# MOSFET_Board.net
KiCad netlist of a schematic drawn in EAGLE
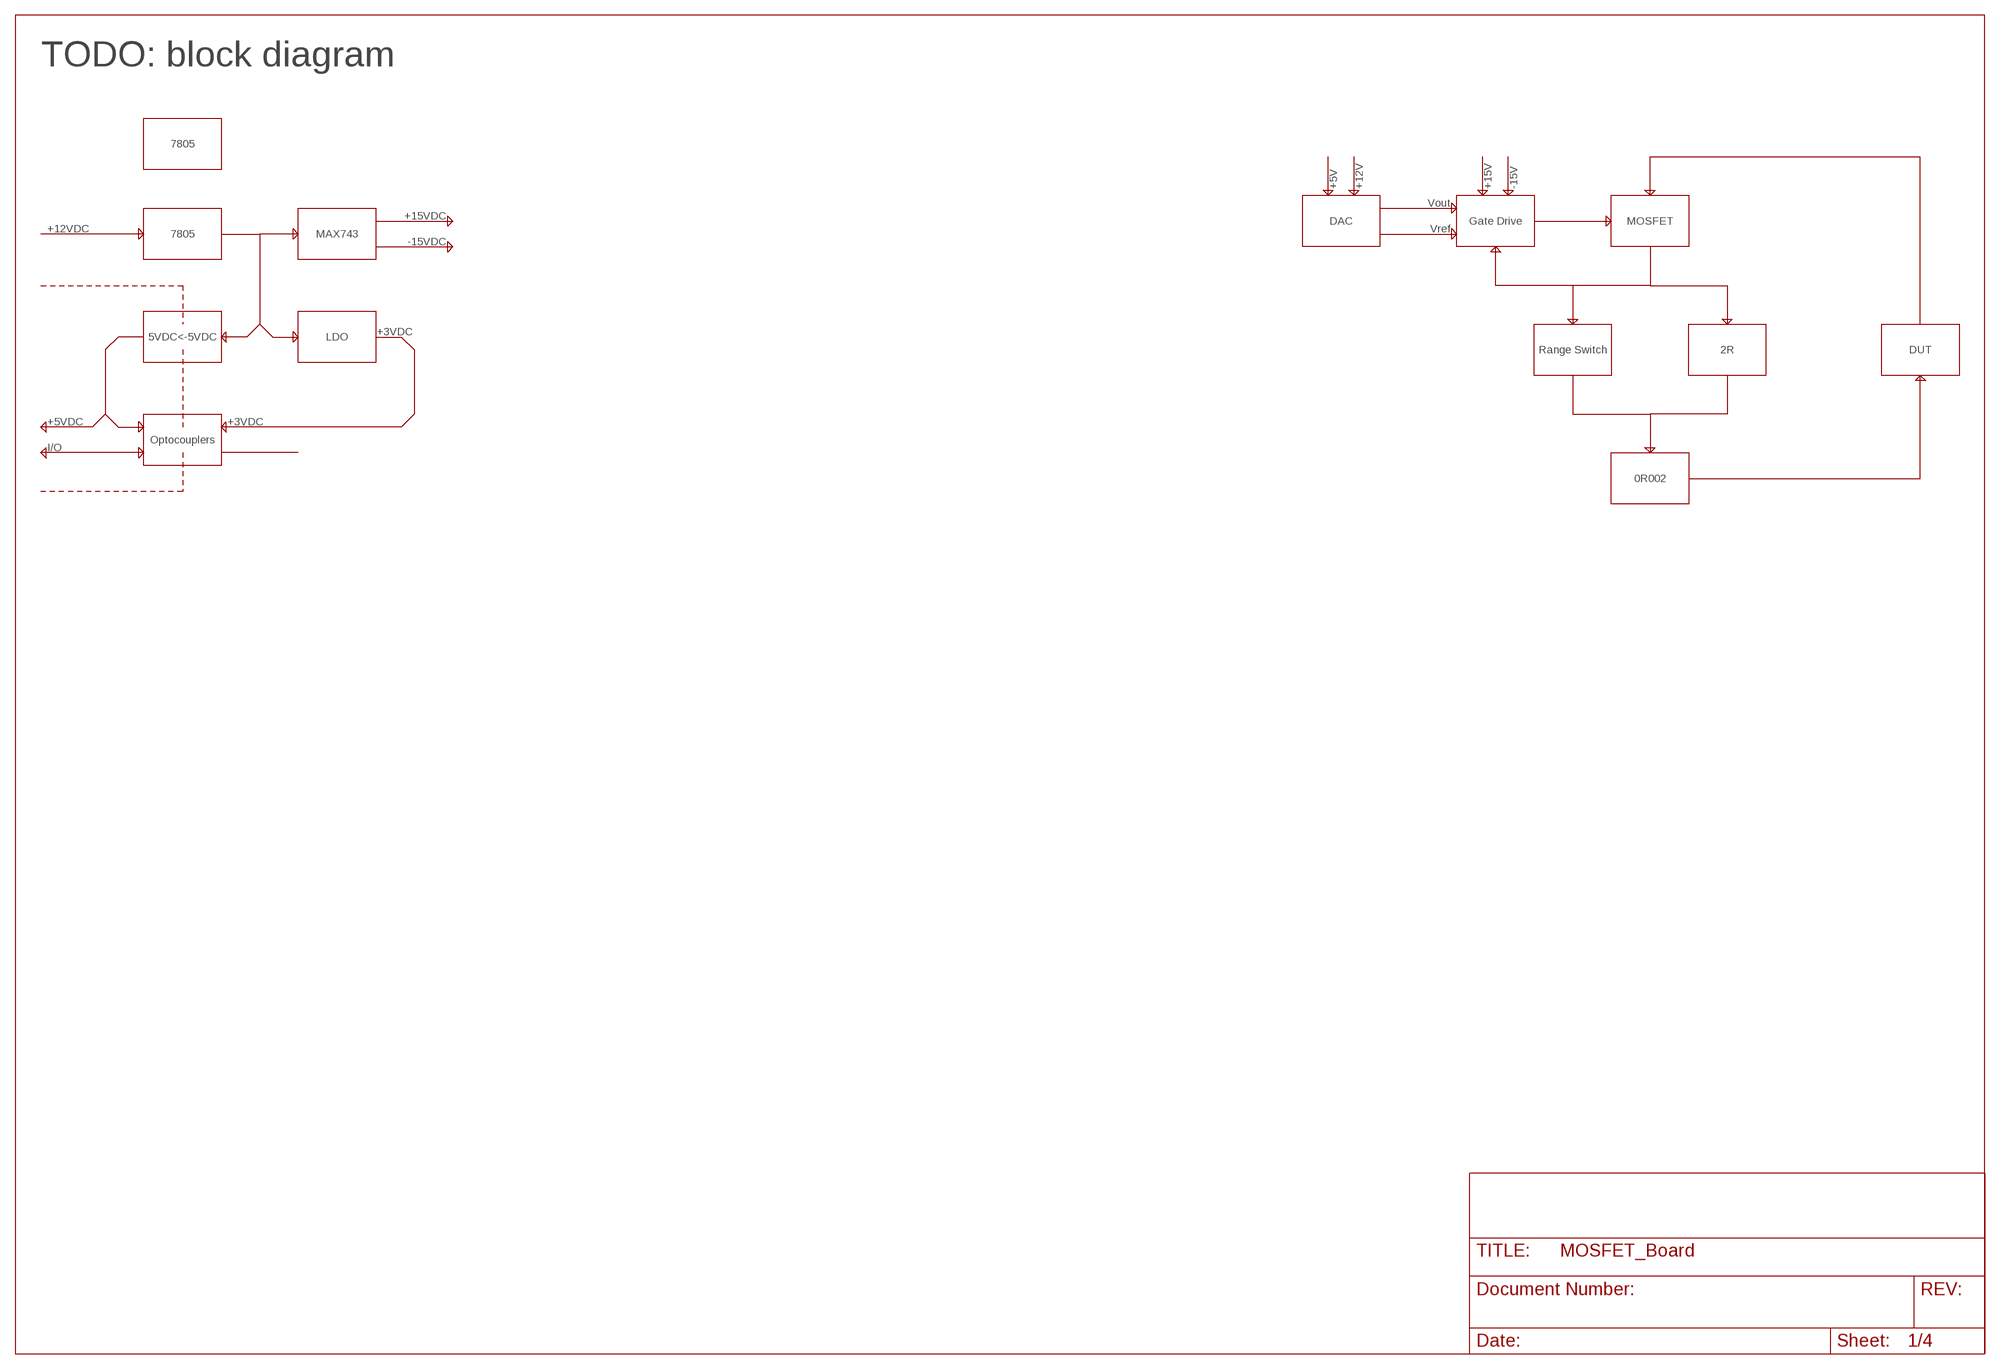
[diagram p0: schematic, sheet 1]
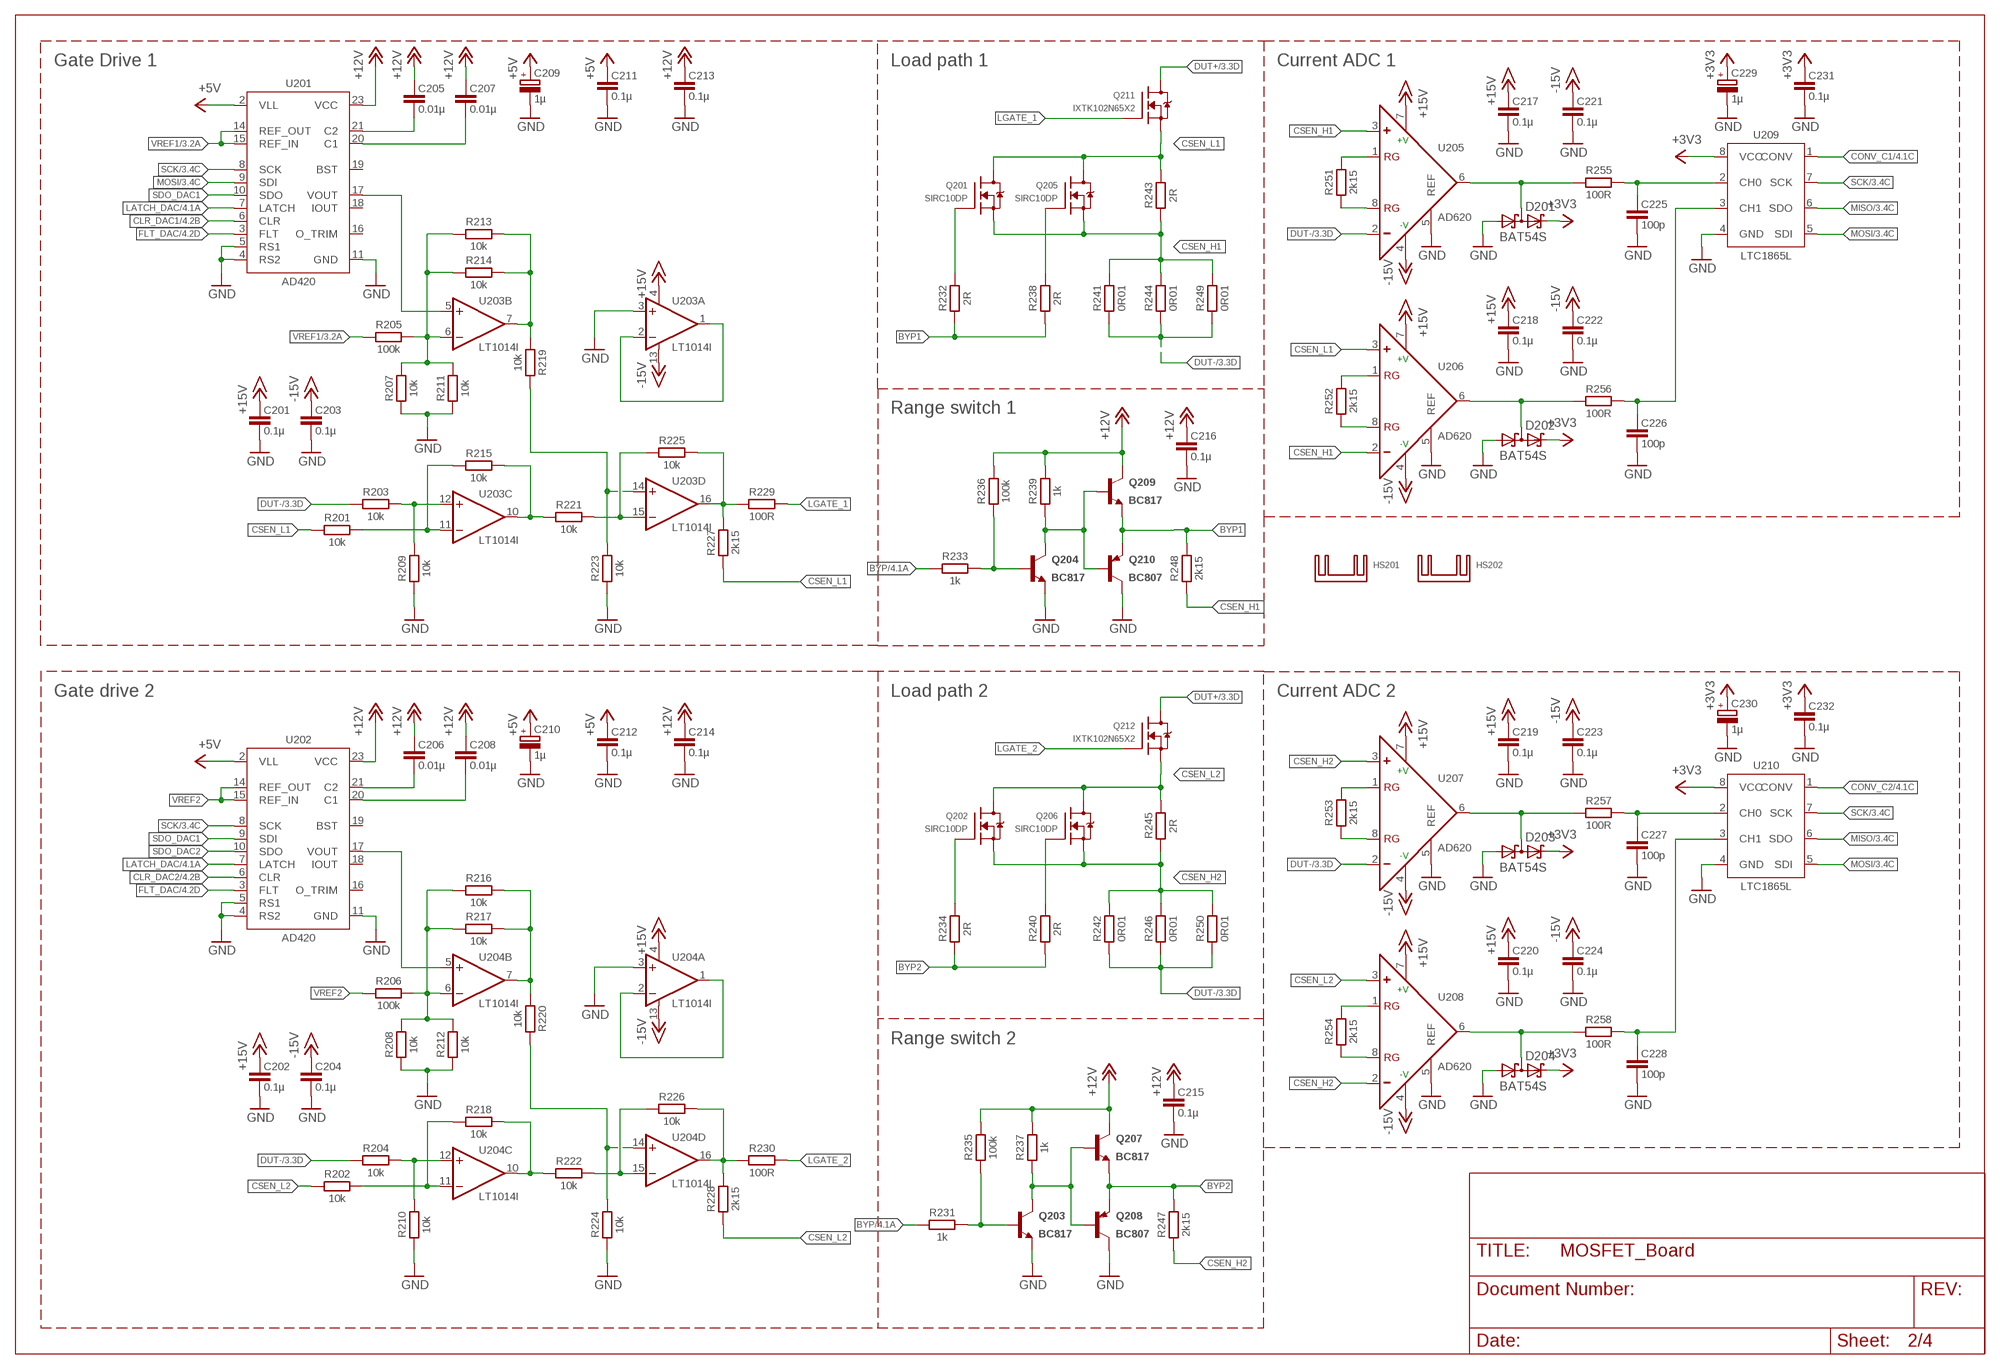
[diagram p1: schematic, sheet 2]
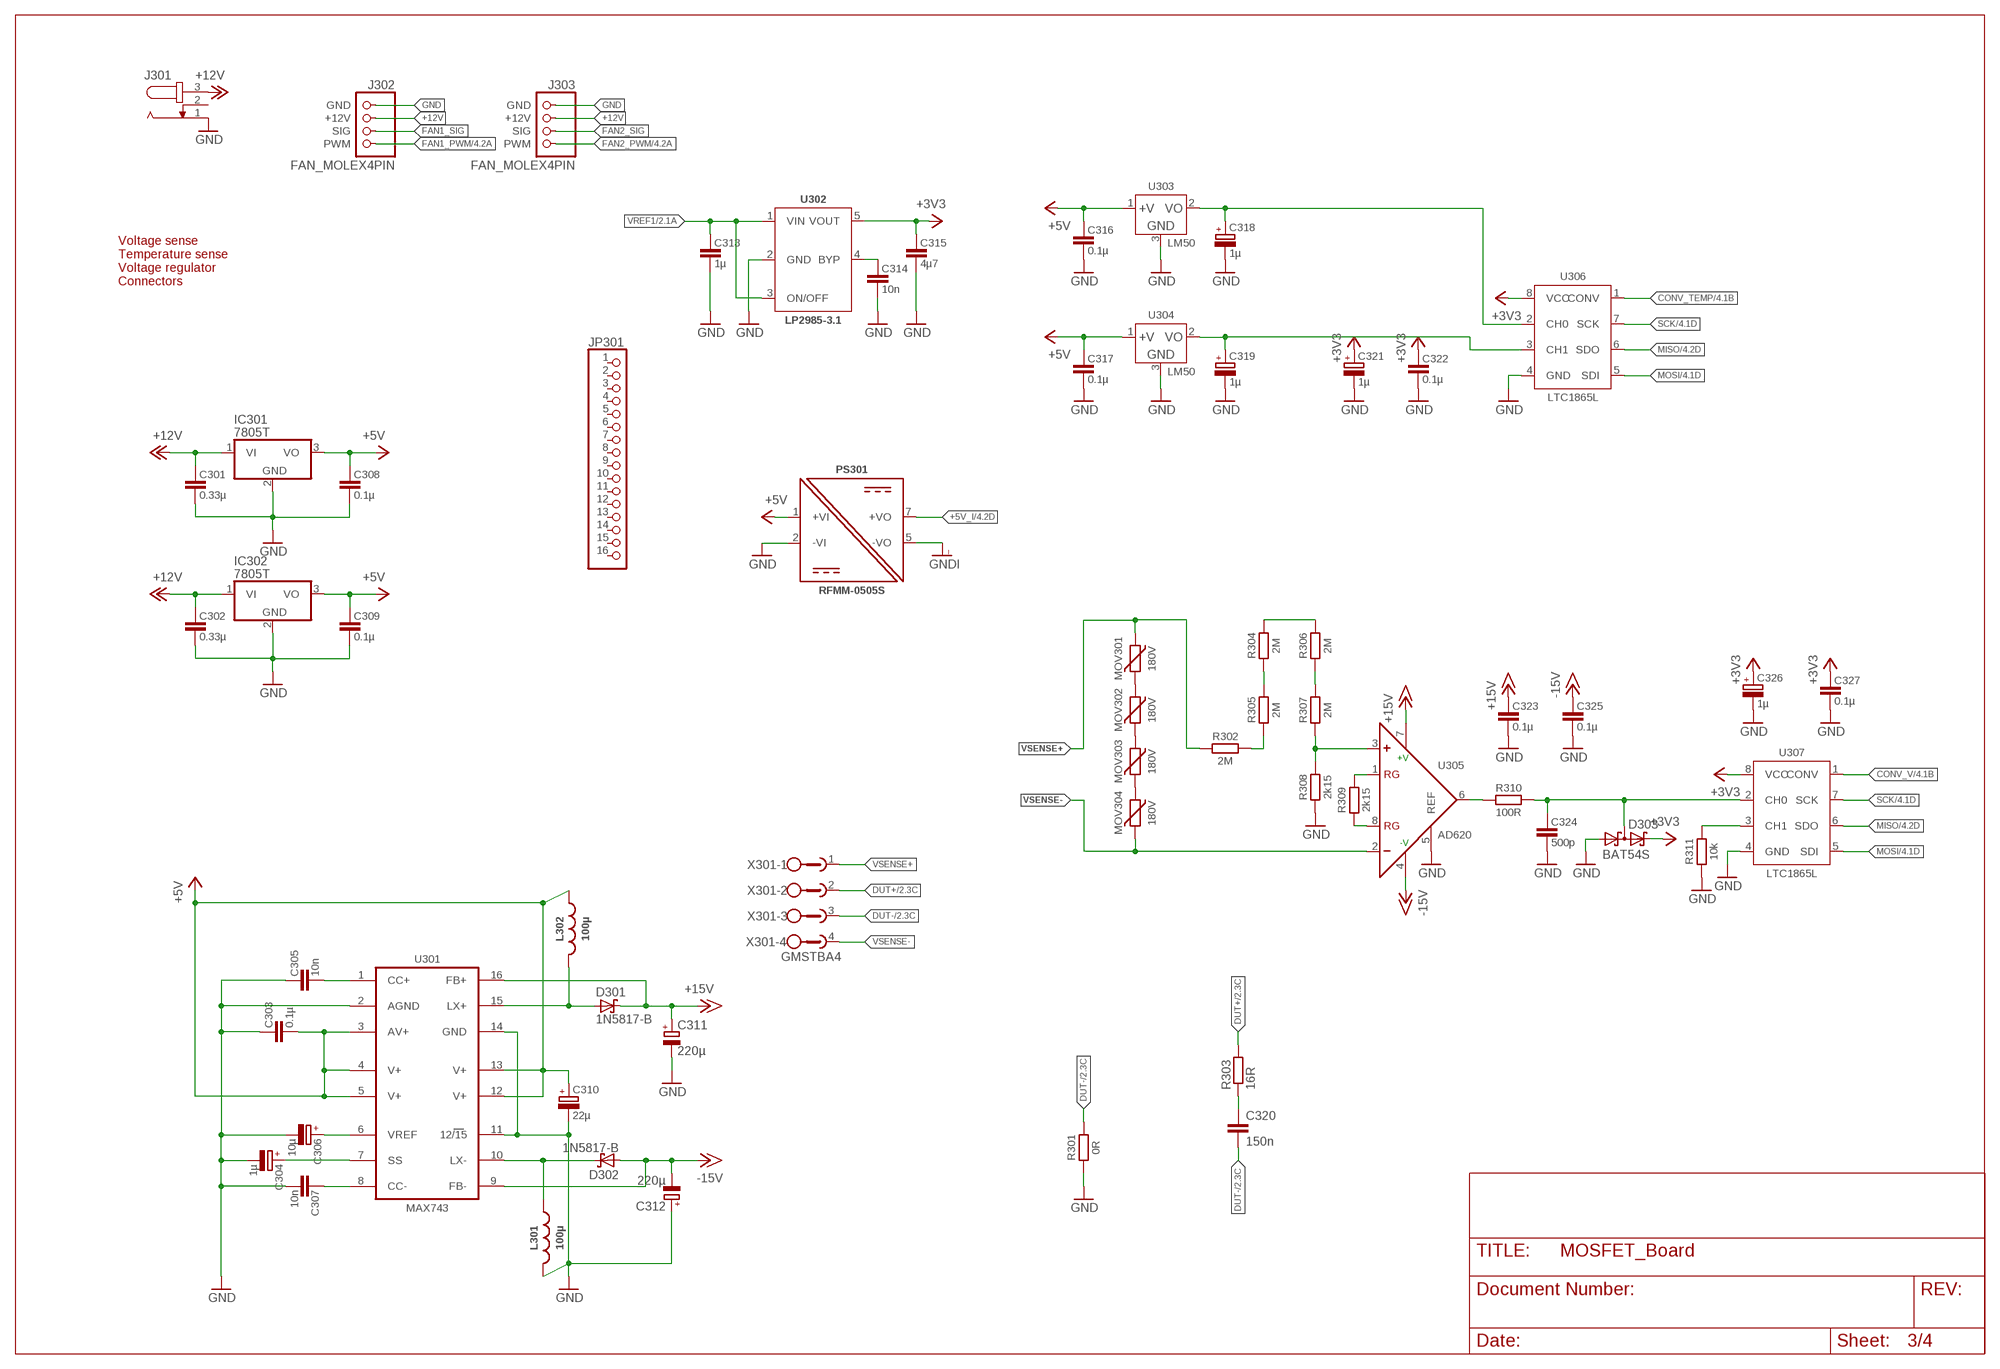
[diagram p2: schematic, sheet 3]
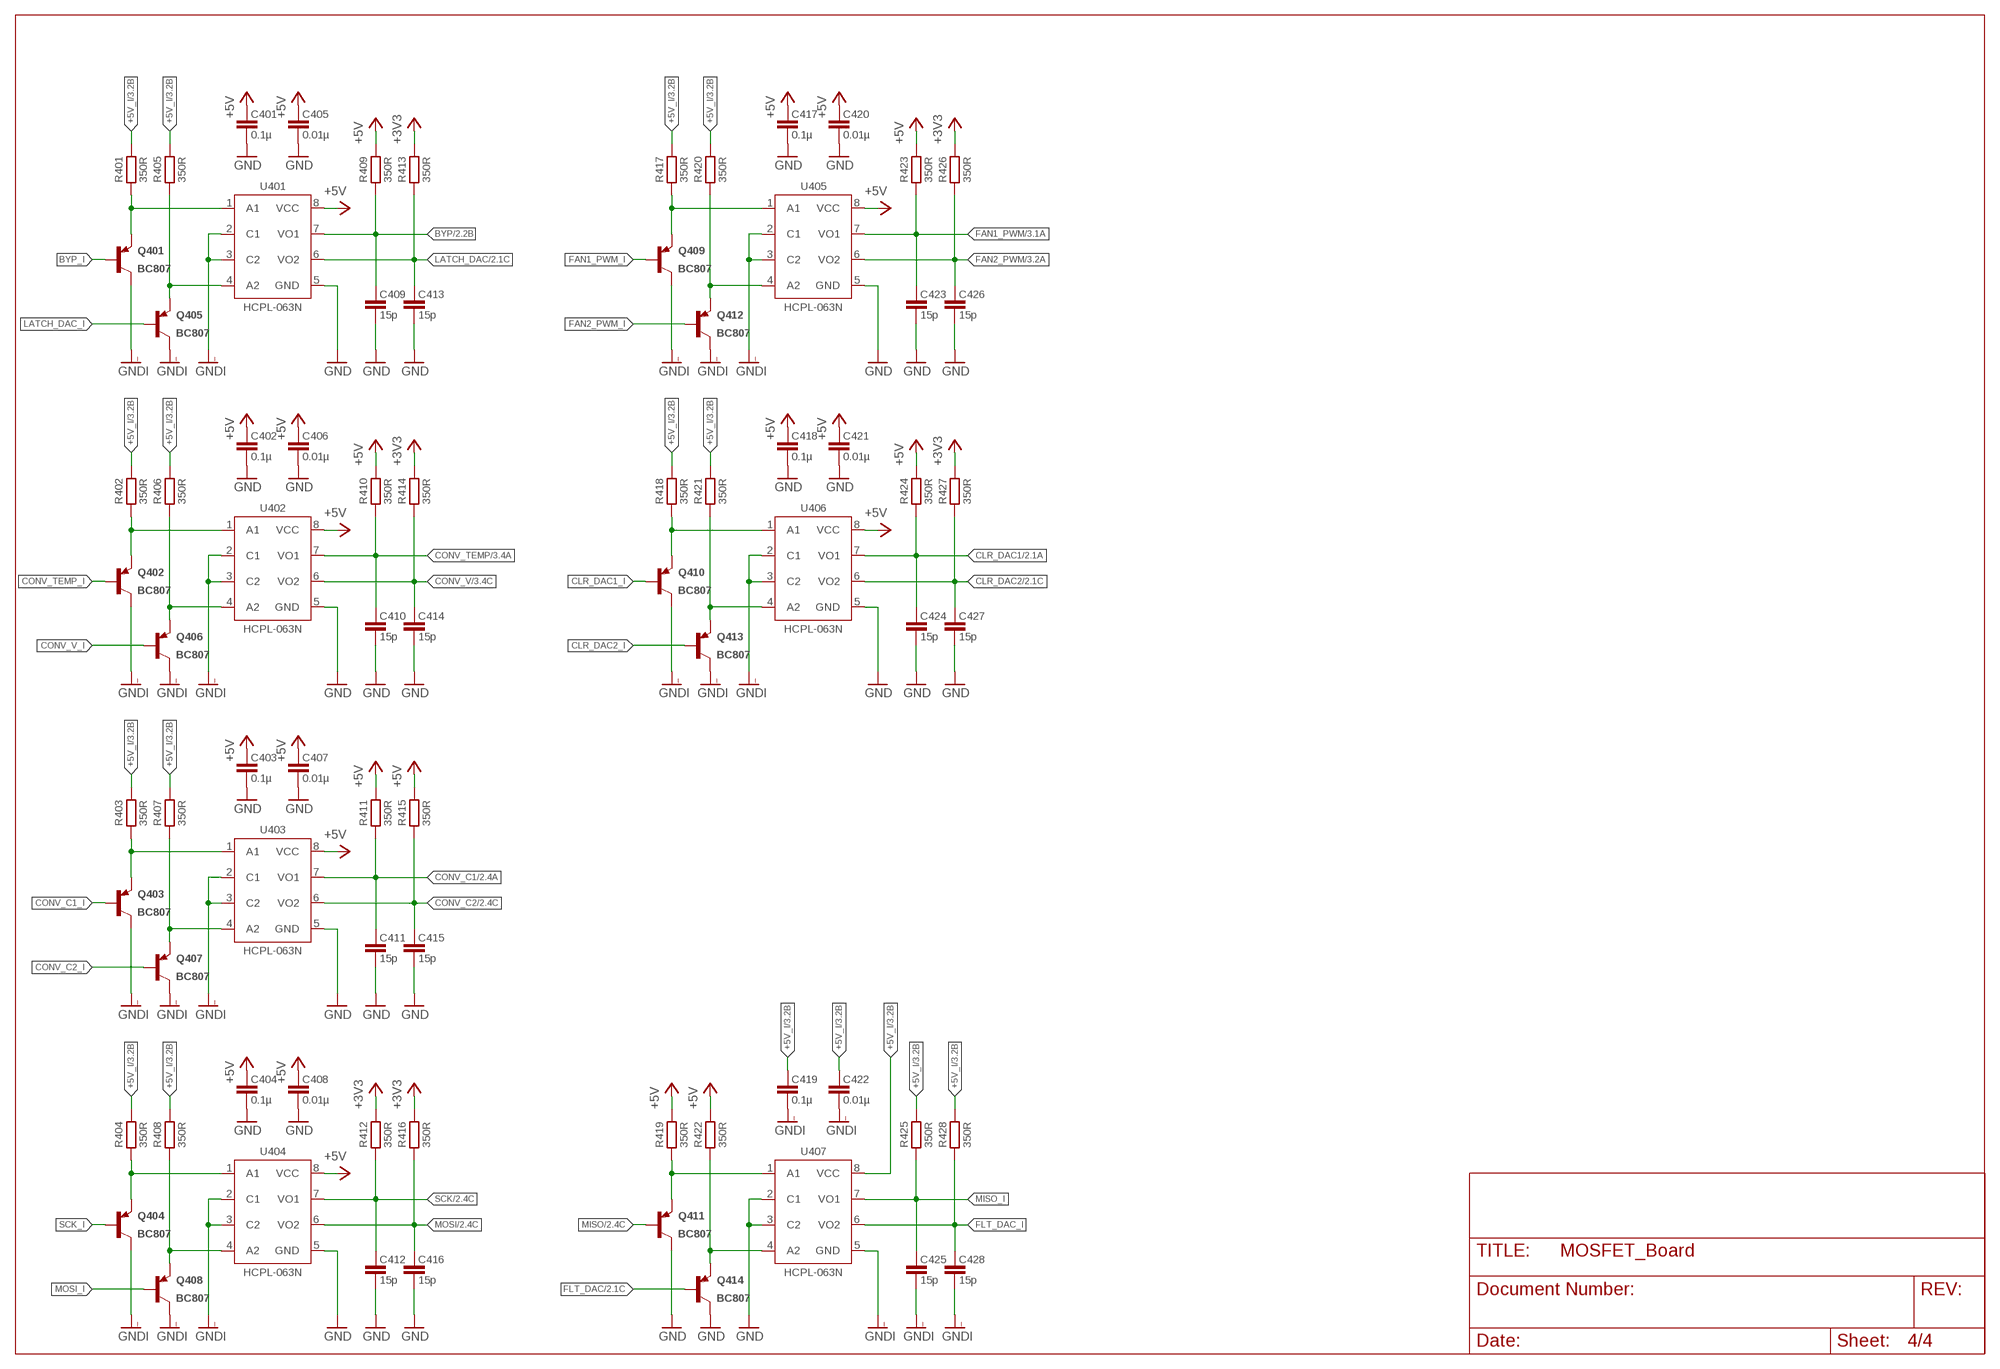
[diagram p3: schematic, sheet 4]

(export (version "E")
  (design (tool "Eeschema 10.0.6"))
  (components
    (comp (ref "C401")
      (value "0.1µ")
      (footprint "eagle-import:C1608")
      (libsource (lib "eagle-import") (part "C-EU-1608"))
    )
    (comp (ref "C402")
      (value "0.1µ")
      (footprint "eagle-import:C1608")
      (libsource (lib "eagle-import") (part "C-EU-1608"))
    )
    (comp (ref "C403")
      (value "0.1µ")
      (footprint "eagle-import:C1608")
      (libsource (lib "eagle-import") (part "C-EU-1608"))
    )
    (comp (ref "C404")
      (value "0.1µ")
      (footprint "eagle-import:C1608")
      (libsource (lib "eagle-import") (part "C-EU-1608"))
    )
    (comp (ref "C405")
      (value "0.01µ")
      (footprint "eagle-import:C3216")
      (libsource (lib "eagle-import") (part "C-EU-3216"))
    )
    (comp (ref "C406")
      (value "0.01µ")
      (footprint "eagle-import:C3216")
      (libsource (lib "eagle-import") (part "C-EU-3216"))
    )
    (comp (ref "C407")
      (value "0.01µ")
      (footprint "eagle-import:C3216")
      (libsource (lib "eagle-import") (part "C-EU-3216"))
    )
    (comp (ref "C408")
      (value "0.01µ")
      (footprint "eagle-import:C3216")
      (libsource (lib "eagle-import") (part "C-EU-3216"))
    )
    (comp (ref "C409")
      (value "15p")
      (footprint "eagle-import:C1608")
      (libsource (lib "eagle-import") (part "C-EU-1608"))
    )
    (comp (ref "C410")
      (value "15p")
      (footprint "eagle-import:C1608")
      (libsource (lib "eagle-import") (part "C-EU-1608"))
    )
    (comp (ref "C411")
      (value "15p")
      (footprint "eagle-import:C1608")
      (libsource (lib "eagle-import") (part "C-EU-1608"))
    )
    (comp (ref "C412")
      (value "15p")
      (footprint "eagle-import:C1608")
      (libsource (lib "eagle-import") (part "C-EU-1608"))
    )
    (comp (ref "C413")
      (value "15p")
      (footprint "eagle-import:C1608")
      (libsource (lib "eagle-import") (part "C-EU-1608"))
    )
    (comp (ref "C414")
      (value "15p")
      (footprint "eagle-import:C1608")
      (libsource (lib "eagle-import") (part "C-EU-1608"))
    )
    (comp (ref "C415")
      (value "15p")
      (footprint "eagle-import:C1608")
      (libsource (lib "eagle-import") (part "C-EU-1608"))
    )
    (comp (ref "C416")
      (value "15p")
      (footprint "eagle-import:C1608")
      (libsource (lib "eagle-import") (part "C-EU-1608"))
    )
    (comp (ref "C417")
      (value "0.1µ")
      (footprint "eagle-import:C1608")
      (libsource (lib "eagle-import") (part "C-EU-1608"))
    )
    (comp (ref "C418")
      (value "0.1µ")
      (footprint "eagle-import:C1608")
      (libsource (lib "eagle-import") (part "C-EU-1608"))
    )
    (comp (ref "C419")
      (value "0.1µ")
      (footprint "eagle-import:C1608")
      (libsource (lib "eagle-import") (part "C-EU-1608"))
    )
    (comp (ref "C420")
      (value "0.01µ")
      (footprint "eagle-import:C3216")
      (libsource (lib "eagle-import") (part "C-EU-3216"))
    )
    (comp (ref "C421")
      (value "0.01µ")
      (footprint "eagle-import:C3216")
      (libsource (lib "eagle-import") (part "C-EU-3216"))
    )
    (comp (ref "C422")
      (value "0.01µ")
      (footprint "eagle-import:C3216")
      (libsource (lib "eagle-import") (part "C-EU-3216"))
    )
    (comp (ref "C423")
      (value "15p")
      (footprint "eagle-import:C1608")
      (libsource (lib "eagle-import") (part "C-EU-1608"))
    )
    (comp (ref "C424")
      (value "15p")
      (footprint "eagle-import:C1608")
      (libsource (lib "eagle-import") (part "C-EU-1608"))
    )
    (comp (ref "C425")
      (value "15p")
      (footprint "eagle-import:C1608")
      (libsource (lib "eagle-import") (part "C-EU-1608"))
    )
    (comp (ref "C426")
      (value "15p")
      (footprint "eagle-import:C1608")
      (libsource (lib "eagle-import") (part "C-EU-1608"))
    )
    (comp (ref "C427")
      (value "15p")
      (footprint "eagle-import:C1608")
      (libsource (lib "eagle-import") (part "C-EU-1608"))
    )
    (comp (ref "C428")
      (value "15p")
      (footprint "eagle-import:C1608")
      (libsource (lib "eagle-import") (part "C-EU-1608"))
    )
    (comp (ref "Q401")
      (value "BC807")
      (footprint "eagle-import:SOT23")
      (libsource (lib "eagle-import") (part "BC807"))
    )
    (comp (ref "Q402")
      (value "BC807")
      (footprint "eagle-import:SOT23")
      (libsource (lib "eagle-import") (part "BC807"))
    )
    (comp (ref "Q403")
      (value "BC807")
      (footprint "eagle-import:SOT23")
      (libsource (lib "eagle-import") (part "BC807"))
    )
    (comp (ref "Q404")
      (value "BC807")
      (footprint "eagle-import:SOT23")
      (libsource (lib "eagle-import") (part "BC807"))
    )
    (comp (ref "Q405")
      (value "BC807")
      (footprint "eagle-import:SOT23")
      (libsource (lib "eagle-import") (part "BC807"))
    )
    (comp (ref "Q406")
      (value "BC807")
      (footprint "eagle-import:SOT23")
      (libsource (lib "eagle-import") (part "BC807"))
    )
    (comp (ref "Q407")
      (value "BC807")
      (footprint "eagle-import:SOT23")
      (libsource (lib "eagle-import") (part "BC807"))
    )
    (comp (ref "Q408")
      (value "BC807")
      (footprint "eagle-import:SOT23")
      (libsource (lib "eagle-import") (part "BC807"))
    )
    (comp (ref "Q409")
      (value "BC807")
      (footprint "eagle-import:SOT23")
      (libsource (lib "eagle-import") (part "BC807"))
    )
    (comp (ref "Q410")
      (value "BC807")
      (footprint "eagle-import:SOT23")
      (libsource (lib "eagle-import") (part "BC807"))
    )
    (comp (ref "Q411")
      (value "BC807")
      (footprint "eagle-import:SOT23")
      (libsource (lib "eagle-import") (part "BC807"))
    )
    (comp (ref "Q412")
      (value "BC807")
      (footprint "eagle-import:SOT23")
      (libsource (lib "eagle-import") (part "BC807"))
    )
    (comp (ref "Q413")
      (value "BC807")
      (footprint "eagle-import:SOT23")
      (libsource (lib "eagle-import") (part "BC807"))
    )
    (comp (ref "Q414")
      (value "BC807")
      (footprint "eagle-import:SOT23")
      (libsource (lib "eagle-import") (part "BC807"))
    )
    (comp (ref "R401")
      (value "350R")
      (footprint "eagle-import:R1608")
      (libsource (lib "eagle-import") (part "R-EU-1608"))
    )
    (comp (ref "R402")
      (value "350R")
      (footprint "eagle-import:R1608")
      (libsource (lib "eagle-import") (part "R-EU-1608"))
    )
    (comp (ref "R403")
      (value "350R")
      (footprint "eagle-import:R1608")
      (libsource (lib "eagle-import") (part "R-EU-1608"))
    )
    (comp (ref "R404")
      (value "350R")
      (footprint "eagle-import:R1608")
      (libsource (lib "eagle-import") (part "R-EU-1608"))
    )
    (comp (ref "R405")
      (value "350R")
      (footprint "eagle-import:R1608")
      (libsource (lib "eagle-import") (part "R-EU-1608"))
    )
    (comp (ref "R406")
      (value "350R")
      (footprint "eagle-import:R1608")
      (libsource (lib "eagle-import") (part "R-EU-1608"))
    )
    (comp (ref "R407")
      (value "350R")
      (footprint "eagle-import:R1608")
      (libsource (lib "eagle-import") (part "R-EU-1608"))
    )
    (comp (ref "R408")
      (value "350R")
      (footprint "eagle-import:R1608")
      (libsource (lib "eagle-import") (part "R-EU-1608"))
    )
    (comp (ref "R409")
      (value "350R")
      (footprint "eagle-import:R1608")
      (libsource (lib "eagle-import") (part "R-EU-1608"))
    )
    (comp (ref "R410")
      (value "350R")
      (footprint "eagle-import:R1608")
      (libsource (lib "eagle-import") (part "R-EU-1608"))
    )
    (comp (ref "R411")
      (value "350R")
      (footprint "eagle-import:R1608")
      (libsource (lib "eagle-import") (part "R-EU-1608"))
    )
    (comp (ref "R412")
      (value "350R")
      (footprint "eagle-import:R1608")
      (libsource (lib "eagle-import") (part "R-EU-1608"))
    )
    (comp (ref "R413")
      (value "350R")
      (footprint "eagle-import:R1608")
      (libsource (lib "eagle-import") (part "R-EU-1608"))
    )
    (comp (ref "R414")
      (value "350R")
      (footprint "eagle-import:R1608")
      (libsource (lib "eagle-import") (part "R-EU-1608"))
    )
    (comp (ref "R415")
      (value "350R")
      (footprint "eagle-import:R1608")
      (libsource (lib "eagle-import") (part "R-EU-1608"))
    )
    (comp (ref "R416")
      (value "350R")
      (footprint "eagle-import:R1608")
      (libsource (lib "eagle-import") (part "R-EU-1608"))
    )
    (comp (ref "R417")
      (value "350R")
      (footprint "eagle-import:R1608")
      (libsource (lib "eagle-import") (part "R-EU-1608"))
    )
    (comp (ref "R418")
      (value "350R")
      (footprint "eagle-import:R1608")
      (libsource (lib "eagle-import") (part "R-EU-1608"))
    )
    (comp (ref "R419")
      (value "350R")
      (footprint "eagle-import:R1608")
      (libsource (lib "eagle-import") (part "R-EU-1608"))
    )
    (comp (ref "R420")
      (value "350R")
      (footprint "eagle-import:R1608")
      (libsource (lib "eagle-import") (part "R-EU-1608"))
    )
    (comp (ref "R421")
      (value "350R")
      (footprint "eagle-import:R1608")
      (libsource (lib "eagle-import") (part "R-EU-1608"))
    )
    (comp (ref "R422")
      (value "350R")
      (footprint "eagle-import:R1608")
      (libsource (lib "eagle-import") (part "R-EU-1608"))
    )
    (comp (ref "R423")
      (value "350R")
      (footprint "eagle-import:R1608")
      (libsource (lib "eagle-import") (part "R-EU-1608"))
    )
    (comp (ref "R424")
      (value "350R")
      (footprint "eagle-import:R1608")
      (libsource (lib "eagle-import") (part "R-EU-1608"))
    )
    (comp (ref "R425")
      (value "350R")
      (footprint "eagle-import:R1608")
      (libsource (lib "eagle-import") (part "R-EU-1608"))
    )
    (comp (ref "R426")
      (value "350R")
      (footprint "eagle-import:R1608")
      (libsource (lib "eagle-import") (part "R-EU-1608"))
    )
    (comp (ref "R427")
      (value "350R")
      (footprint "eagle-import:R1608")
      (libsource (lib "eagle-import") (part "R-EU-1608"))
    )
    (comp (ref "R428")
      (value "350R")
      (footprint "eagle-import:R1608")
      (libsource (lib "eagle-import") (part "R-EU-1608"))
    )
    (comp (ref "U401")
      (value "HCPL-063N")
      (footprint "eagle-import:SO8")
      (libsource (lib "eagle-import") (part "HCPL-063N"))
    )
    (comp (ref "U402")
      (value "HCPL-063N")
      (footprint "eagle-import:SO8")
      (libsource (lib "eagle-import") (part "HCPL-063N"))
    )
    (comp (ref "U403")
      (value "HCPL-063N")
      (footprint "eagle-import:SO8")
      (libsource (lib "eagle-import") (part "HCPL-063N"))
    )
    (comp (ref "U404")
      (value "HCPL-063N")
      (footprint "eagle-import:SO8")
      (libsource (lib "eagle-import") (part "HCPL-063N"))
    )
    (comp (ref "U405")
      (value "HCPL-063N")
      (footprint "eagle-import:SO8")
      (libsource (lib "eagle-import") (part "HCPL-063N"))
    )
    (comp (ref "U406")
      (value "HCPL-063N")
      (footprint "eagle-import:SO8")
      (libsource (lib "eagle-import") (part "HCPL-063N"))
    )
    (comp (ref "U407")
      (value "HCPL-063N")
      (footprint "eagle-import:SO8")
      (libsource (lib "eagle-import") (part "HCPL-063N"))
    )
    (comp (ref "C301")
      (value "0.33µ")
      (footprint "eagle-import:C3216")
      (libsource (lib "eagle-import") (part "C-EU-3216"))
    )
    (comp (ref "C302")
      (value "0.33µ")
      (footprint "eagle-import:C3216")
      (libsource (lib "eagle-import") (part "C-EU-3216"))
    )
    (comp (ref "C303")
      (value "0.1µ")
      (footprint "eagle-import:C3216")
      (libsource (lib "eagle-import") (part "C-EU-3216"))
    )
    (comp (ref "C304")
      (value "1µ")
      (footprint "eagle-import:CT3216")
      (libsource (lib "eagle-import") (part "CPOL-3216-A"))
    )
    (comp (ref "C305")
      (value "10n")
      (footprint "eagle-import:C2012")
      (libsource (lib "eagle-import") (part "C-EU-2012"))
    )
    (comp (ref "C306")
      (value "10µ")
      (footprint "eagle-import:CT6032")
      (libsource (lib "eagle-import") (part "CPOL-6032-C"))
    )
    (comp (ref "C307")
      (value "10n")
      (footprint "eagle-import:C2012")
      (libsource (lib "eagle-import") (part "C-EU-2012"))
    )
    (comp (ref "C308")
      (value "0.1µ")
      (footprint "eagle-import:C1608")
      (libsource (lib "eagle-import") (part "C-EU-1608"))
    )
    (comp (ref "C309")
      (value "0.1µ")
      (footprint "eagle-import:C1608")
      (libsource (lib "eagle-import") (part "C-EU-1608"))
    )
    (comp (ref "C310")
      (value "22µ")
      (footprint "eagle-import:CT6032")
      (libsource (lib "eagle-import") (part "CPOL-6032-C"))
    )
    (comp (ref "C311")
      (value "220µ")
      (footprint "eagle-import:E3,5-10")
      (libsource (lib "eagle-import") (part "CPOL-EUE3.5-10"))
    )
    (comp (ref "C312")
      (value "220µ")
      (footprint "eagle-import:E3,5-10")
      (libsource (lib "eagle-import") (part "CPOL-EUE3.5-10"))
    )
    (comp (ref "C313")
      (value "1µ")
      (footprint "eagle-import:C3216")
      (libsource (lib "eagle-import") (part "C-EU-3216"))
    )
    (comp (ref "C314")
      (value "10n")
      (footprint "eagle-import:C2012")
      (libsource (lib "eagle-import") (part "C-EU-2012"))
    )
    (comp (ref "C315")
      (value "4µ7")
      (footprint "eagle-import:C3216")
      (libsource (lib "eagle-import") (part "C-EU-3216"))
    )
    (comp (ref "C316")
      (value "0.1µ")
      (footprint "eagle-import:C3216")
      (libsource (lib "eagle-import") (part "C-EU-3216"))
    )
    (comp (ref "C317")
      (value "0.1µ")
      (footprint "eagle-import:C3216")
      (libsource (lib "eagle-import") (part "C-EU-3216"))
    )
    (comp (ref "C318")
      (value "1µ")
      (footprint "eagle-import:CT3216")
      (libsource (lib "eagle-import") (part "CPOL-3216-A"))
    )
    (comp (ref "C319")
      (value "1µ")
      (footprint "eagle-import:CT3216")
      (libsource (lib "eagle-import") (part "CPOL-3216-A"))
    )
    (comp (ref "C320")
      (value "150n")
      (footprint "eagle-import:C050-030X075")
      (libsource (lib "eagle-import") (part "C-EU050-030X075"))
    )
    (comp (ref "C321")
      (value "1µ")
      (footprint "eagle-import:CT3216")
      (libsource (lib "eagle-import") (part "CPOL-3216-A"))
    )
    (comp (ref "C322")
      (value "0.1µ")
      (footprint "eagle-import:C3216")
      (libsource (lib "eagle-import") (part "C-EU-3216"))
    )
    (comp (ref "C323")
      (value "0.1µ")
      (footprint "eagle-import:C3216")
      (libsource (lib "eagle-import") (part "C-EU-3216"))
    )
    (comp (ref "C324")
      (value "500p")
      (footprint "eagle-import:C1608")
      (libsource (lib "eagle-import") (part "C-EU-1608"))
    )
    (comp (ref "C325")
      (value "0.1µ")
      (footprint "eagle-import:C3216")
      (libsource (lib "eagle-import") (part "C-EU-3216"))
    )
    (comp (ref "C326")
      (value "1µ")
      (footprint "eagle-import:CT3216")
      (libsource (lib "eagle-import") (part "CPOL-3216-A"))
    )
    (comp (ref "C327")
      (value "0.1µ")
      (footprint "eagle-import:C3216")
      (libsource (lib "eagle-import") (part "C-EU-3216"))
    )
    (comp (ref "D301")
      (value "1N5817-B")
      (footprint "eagle-import:DO41-7.6")
      (libsource (lib "eagle-import") (part "1N5817-B"))
    )
    (comp (ref "D302")
      (value "1N5817-B")
      (footprint "eagle-import:DO41-7.6")
      (libsource (lib "eagle-import") (part "1N5817-B"))
    )
    (comp (ref "D303")
      (value "BAT54S")
      (footprint "eagle-import:SOT23")
      (libsource (lib "eagle-import") (part "BAT54S"))
    )
    (comp (ref "IC301")
      (value "7805T")
      (footprint "eagle-import:TO220H")
      (libsource (lib "eagle-import") (part "78T05"))
    )
    (comp (ref "IC302")
      (value "7805T")
      (footprint "eagle-import:TO220H")
      (libsource (lib "eagle-import") (part "78T05"))
    )
    (comp (ref "J301")
      (value "JACK-PLUG1")
      (footprint "eagle-import:SPC4078")
      (libsource (lib "eagle-import") (part "JACK-PLUG1"))
    )
    (comp (ref "J302")
      (value "FAN_MOLEX4PIN")
      (footprint "eagle-import:MOLEX_47053-1000")
      (libsource (lib "eagle-import") (part "FAN_MOLEX4PIN"))
    )
    (comp (ref "J303")
      (value "FAN_MOLEX4PIN")
      (footprint "eagle-import:MOLEX_47053-1000")
      (libsource (lib "eagle-import") (part "FAN_MOLEX4PIN"))
    )
    (comp (ref "JP301")
      (value "PINHD-1X16")
      (footprint "eagle-import:1X16")
      (libsource (lib "eagle-import") (part "PINHD-1X16"))
    )
    (comp (ref "L301")
      (value "100µ")
      (footprint "eagle-import:MSS1260")
      (libsource (lib "eagle-import") (part "L-EU_MSS1260"))
    )
    (comp (ref "L302")
      (value "100µ")
      (footprint "eagle-import:MSS1260")
      (libsource (lib "eagle-import") (part "L-EU_MSS1260"))
    )
    (comp (ref "MOV301")
      (value "180V")
      (footprint "eagle-import:R3225W")
      (libsource (lib "eagle-import") (part "MOV-3225"))
    )
    (comp (ref "MOV302")
      (value "180V")
      (footprint "eagle-import:R3225W")
      (libsource (lib "eagle-import") (part "MOV-3225"))
    )
    (comp (ref "MOV303")
      (value "180V")
      (footprint "eagle-import:R3225W")
      (libsource (lib "eagle-import") (part "MOV-3225"))
    )
    (comp (ref "MOV304")
      (value "180V")
      (footprint "eagle-import:R3225W")
      (libsource (lib "eagle-import") (part "MOV-3225"))
    )
    (comp (ref "PS301")
      (value "RFMM-0505S")
      (footprint "eagle-import:RECOM-SIP7")
      (libsource (lib "eagle-import") (part "RFMM-0505S"))
    )
    (comp (ref "R301")
      (value "0R")
      (footprint "eagle-import:R3216W")
      (libsource (lib "eagle-import") (part "R-EU-3216"))
    )
    (comp (ref "R302")
      (value "2M")
      (footprint "eagle-import:R3216W")
      (libsource (lib "eagle-import") (part "R-EU-3216"))
    )
    (comp (ref "R303")
      (value "16R")
      (footprint "eagle-import:0204_7")
      (libsource (lib "eagle-import") (part "R-EU_0204/7"))
    )
    (comp (ref "R304")
      (value "2M")
      (footprint "eagle-import:R3216W")
      (libsource (lib "eagle-import") (part "R-EU-3216"))
    )
    (comp (ref "R305")
      (value "2M")
      (footprint "eagle-import:R3216W")
      (libsource (lib "eagle-import") (part "R-EU-3216"))
    )
    (comp (ref "R306")
      (value "2M")
      (footprint "eagle-import:R3216W")
      (libsource (lib "eagle-import") (part "R-EU-3216"))
    )
    (comp (ref "R307")
      (value "2M")
      (footprint "eagle-import:R3216W")
      (libsource (lib "eagle-import") (part "R-EU-3216"))
    )
    (comp (ref "R308")
      (value "2k15")
      (footprint "eagle-import:R2012W")
      (libsource (lib "eagle-import") (part "R-EU-2012"))
    )
    (comp (ref "R309")
      (value "2k15")
      (footprint "eagle-import:R2012W")
      (libsource (lib "eagle-import") (part "R-EU-2012"))
    )
    (comp (ref "R310")
      (value "100R")
      (footprint "eagle-import:R2012W")
      (libsource (lib "eagle-import") (part "R-EU-2012"))
    )
    (comp (ref "R311")
      (value "10k")
      (footprint "eagle-import:R1608")
      (libsource (lib "eagle-import") (part "R-EU-1608"))
    )
    (comp (ref "U301")
      (value "MAX743")
      (footprint "eagle-import:SO16W")
      (libsource (lib "eagle-import") (part "MAX743WE"))
    )
    (comp (ref "U302")
      (value "LP2985-3.1")
      (footprint "eagle-import:SOT23-5L")
      (libsource (lib "eagle-import") (part "LP2985-3.1"))
    )
    (comp (ref "U303")
      (value "LM50")
      (footprint "eagle-import:SOT23W")
      (libsource (lib "eagle-import") (part "LM50"))
    )
    (comp (ref "U304")
      (value "LM50")
      (footprint "eagle-import:SOT23W")
      (libsource (lib "eagle-import") (part "LM50"))
    )
    (comp (ref "U305")
      (value "AD620")
      (footprint "eagle-import:SO8")
      (libsource (lib "eagle-import") (part "AD620R-8"))
    )
    (comp (ref "U306")
      (value "LTC1865L")
      (footprint "eagle-import:SO8")
      (libsource (lib "eagle-import") (part "LTC1865L"))
    )
    (comp (ref "U307")
      (value "LTC1865L")
      (footprint "eagle-import:SO8")
      (libsource (lib "eagle-import") (part "LTC1865L"))
    )
    (comp (ref "X301")
      (value "GMSTBA4")
      (footprint "eagle-import:GMSTBA4")
      (fields (field (name "MF") "FARNELL") (field (name "MPN") "1757268"))
      (libsource (lib "eagle-import") (part "GMSTBA4"))
    )
    (comp (ref "C201")
      (value "0.1µ")
      (footprint "eagle-import:C1608")
      (libsource (lib "eagle-import") (part "C-EU-1608"))
    )
    (comp (ref "C202")
      (value "0.1µ")
      (footprint "eagle-import:C1608")
      (libsource (lib "eagle-import") (part "C-EU-1608"))
    )
    (comp (ref "C203")
      (value "0.1µ")
      (footprint "eagle-import:C1608")
      (libsource (lib "eagle-import") (part "C-EU-1608"))
    )
    (comp (ref "C204")
      (value "0.1µ")
      (footprint "eagle-import:C1608")
      (libsource (lib "eagle-import") (part "C-EU-1608"))
    )
    (comp (ref "C205")
      (value "0.01µ")
      (footprint "eagle-import:C2012")
      (libsource (lib "eagle-import") (part "C-EU-2012"))
    )
    (comp (ref "C206")
      (value "0.01µ")
      (footprint "eagle-import:C3216")
      (libsource (lib "eagle-import") (part "C-EU-3216"))
    )
    (comp (ref "C207")
      (value "0.01µ")
      (footprint "eagle-import:C2012")
      (libsource (lib "eagle-import") (part "C-EU-2012"))
    )
    (comp (ref "C208")
      (value "0.01µ")
      (footprint "eagle-import:C3216")
      (libsource (lib "eagle-import") (part "C-EU-3216"))
    )
    (comp (ref "C209")
      (value "1µ")
      (footprint "eagle-import:CT3216")
      (libsource (lib "eagle-import") (part "CPOL-3216-A"))
    )
    (comp (ref "C210")
      (value "1µ")
      (footprint "eagle-import:CT3216")
      (libsource (lib "eagle-import") (part "CPOL-3216-A"))
    )
    (comp (ref "C211")
      (value "0.1µ")
      (footprint "eagle-import:C1608")
      (libsource (lib "eagle-import") (part "C-EU-1608"))
    )
    (comp (ref "C212")
      (value "0.1µ")
      (footprint "eagle-import:C1608")
      (libsource (lib "eagle-import") (part "C-EU-1608"))
    )
    (comp (ref "C213")
      (value "0.1µ")
      (footprint "eagle-import:C1608")
      (libsource (lib "eagle-import") (part "C-EU-1608"))
    )
    (comp (ref "C214")
      (value "0.1µ")
      (footprint "eagle-import:C1608")
      (libsource (lib "eagle-import") (part "C-EU-1608"))
    )
    (comp (ref "C215")
      (value "0.1µ")
      (footprint "eagle-import:C1608")
      (libsource (lib "eagle-import") (part "C-EU-1608"))
    )
    (comp (ref "C216")
      (value "0.1µ")
      (footprint "eagle-import:C1608")
      (libsource (lib "eagle-import") (part "C-EU-1608"))
    )
    (comp (ref "C217")
      (value "0.1µ")
      (footprint "eagle-import:C1608")
      (libsource (lib "eagle-import") (part "C-EU-1608"))
    )
    (comp (ref "C218")
      (value "0.1µ")
      (footprint "eagle-import:C1608")
      (libsource (lib "eagle-import") (part "C-EU-1608"))
    )
    (comp (ref "C219")
      (value "0.1µ")
      (footprint "eagle-import:C1608")
      (libsource (lib "eagle-import") (part "C-EU-1608"))
    )
    (comp (ref "C220")
      (value "0.1µ")
      (footprint "eagle-import:C1608")
      (libsource (lib "eagle-import") (part "C-EU-1608"))
    )
    (comp (ref "C221")
      (value "0.1µ")
      (footprint "eagle-import:C1608")
      (libsource (lib "eagle-import") (part "C-EU-1608"))
    )
    (comp (ref "C222")
      (value "0.1µ")
      (footprint "eagle-import:C1608")
      (libsource (lib "eagle-import") (part "C-EU-1608"))
    )
    (comp (ref "C223")
      (value "0.1µ")
      (footprint "eagle-import:C1608")
      (libsource (lib "eagle-import") (part "C-EU-1608"))
    )
    (comp (ref "C224")
      (value "0.1µ")
      (footprint "eagle-import:C1608")
      (libsource (lib "eagle-import") (part "C-EU-1608"))
    )
    (comp (ref "C225")
      (value "100p")
      (footprint "eagle-import:C1608")
      (libsource (lib "eagle-import") (part "C-EU-1608"))
    )
    (comp (ref "C226")
      (value "100p")
      (footprint "eagle-import:C1608")
      (libsource (lib "eagle-import") (part "C-EU-1608"))
    )
    (comp (ref "C227")
      (value "100p")
      (footprint "eagle-import:C1608")
      (libsource (lib "eagle-import") (part "C-EU-1608"))
    )
    (comp (ref "C228")
      (value "100p")
      (footprint "eagle-import:C1608")
      (libsource (lib "eagle-import") (part "C-EU-1608"))
    )
    (comp (ref "C229")
      (value "1µ")
      (footprint "eagle-import:CT3216")
      (libsource (lib "eagle-import") (part "CPOL-3216-A"))
    )
    (comp (ref "C230")
      (value "1µ")
      (footprint "eagle-import:CT3216")
      (libsource (lib "eagle-import") (part "CPOL-3216-A"))
    )
    (comp (ref "C231")
      (value "0.1µ")
      (footprint "eagle-import:C1608")
      (libsource (lib "eagle-import") (part "C-EU-1608"))
    )
    (comp (ref "C232")
      (value "0.1µ")
      (footprint "eagle-import:C1608")
      (libsource (lib "eagle-import") (part "C-EU-1608"))
    )
    (comp (ref "D201")
      (value "BAT54S")
      (footprint "eagle-import:SOT23")
      (libsource (lib "eagle-import") (part "BAT54S"))
    )
    (comp (ref "D202")
      (value "BAT54S")
      (footprint "eagle-import:SOT23")
      (libsource (lib "eagle-import") (part "BAT54S"))
    )
    (comp (ref "D203")
      (value "BAT54S")
      (footprint "eagle-import:SOT23")
      (libsource (lib "eagle-import") (part "BAT54S"))
    )
    (comp (ref "D204")
      (value "BAT54S")
      (footprint "eagle-import:SOT23")
      (libsource (lib "eagle-import") (part "BAT54S"))
    )
    (comp (ref "HS201")
      (value "HEATSINK-LGA115X")
      (footprint "eagle-import:HEATSINK-LGA115X")
      (libsource (lib "eagle-import") (part "HEATSINK-LGA115X"))
    )
    (comp (ref "HS202")
      (value "HEATSINK-LGA115X")
      (footprint "eagle-import:HEATSINK-LGA115X")
      (libsource (lib "eagle-import") (part "HEATSINK-LGA115X"))
    )
    (comp (ref "Q201")
      (value "SIRC10DP")
      (footprint "eagle-import:POWERPAK-SO-8")
      (libsource (lib "eagle-import") (part "SIRC10DP"))
    )
    (comp (ref "Q202")
      (value "SIRC10DP")
      (footprint "eagle-import:POWERPAK-SO-8")
      (libsource (lib "eagle-import") (part "SIRC10DP"))
    )
    (comp (ref "Q203")
      (value "BC817")
      (footprint "eagle-import:SOT23")
      (libsource (lib "eagle-import") (part "BC817"))
    )
    (comp (ref "Q204")
      (value "BC817")
      (footprint "eagle-import:SOT23")
      (libsource (lib "eagle-import") (part "BC817"))
    )
    (comp (ref "Q205")
      (value "SIRC10DP")
      (footprint "eagle-import:POWERPAK-SO-8")
      (libsource (lib "eagle-import") (part "SIRC10DP"))
    )
    (comp (ref "Q206")
      (value "SIRC10DP")
      (footprint "eagle-import:POWERPAK-SO-8")
      (libsource (lib "eagle-import") (part "SIRC10DP"))
    )
    (comp (ref "Q207")
      (value "BC817")
      (footprint "eagle-import:SOT23")
      (libsource (lib "eagle-import") (part "BC817"))
    )
    (comp (ref "Q208")
      (value "BC807")
      (footprint "eagle-import:SOT23")
      (libsource (lib "eagle-import") (part "BC807"))
    )
    (comp (ref "Q209")
      (value "BC817")
      (footprint "eagle-import:SOT23")
      (libsource (lib "eagle-import") (part "BC817"))
    )
    (comp (ref "Q210")
      (value "BC807")
      (footprint "eagle-import:SOT23")
      (libsource (lib "eagle-import") (part "BC807"))
    )
    (comp (ref "Q211")
      (value "IXTK102N65X2")
      (footprint "eagle-import:TO-264P-H-PADUP")
      (libsource (lib "eagle-import") (part "IXTK102N65X2R"))
    )
    (comp (ref "Q212")
      (value "IXTK102N65X2")
      (footprint "eagle-import:TO-264P-H-PADUP")
      (libsource (lib "eagle-import") (part "IXTK102N65X2R"))
    )
    (comp (ref "R201")
      (value "10k")
      (footprint "eagle-import:R1608")
      (libsource (lib "eagle-import") (part "R-EU-1608"))
    )
    (comp (ref "R202")
      (value "10k")
      (footprint "eagle-import:R1608")
      (libsource (lib "eagle-import") (part "R-EU-1608"))
    )
    (comp (ref "R203")
      (value "10k")
      (footprint "eagle-import:R1608")
      (libsource (lib "eagle-import") (part "R-EU-1608"))
    )
    (comp (ref "R204")
      (value "10k")
      (footprint "eagle-import:R1608")
      (libsource (lib "eagle-import") (part "R-EU-1608"))
    )
    (comp (ref "R205")
      (value "100k")
      (footprint "eagle-import:R1608")
      (libsource (lib "eagle-import") (part "R-EU-1608"))
    )
    (comp (ref "R206")
      (value "100k")
      (footprint "eagle-import:R1608")
      (libsource (lib "eagle-import") (part "R-EU-1608"))
    )
    (comp (ref "R207")
      (value "10k")
      (footprint "eagle-import:R1608")
      (libsource (lib "eagle-import") (part "R-EU-1608"))
    )
    (comp (ref "R208")
      (value "10k")
      (footprint "eagle-import:R1608")
      (libsource (lib "eagle-import") (part "R-EU-1608"))
    )
    (comp (ref "R209")
      (value "10k")
      (footprint "eagle-import:R1608")
      (libsource (lib "eagle-import") (part "R-EU-1608"))
    )
    (comp (ref "R210")
      (value "10k")
      (footprint "eagle-import:R1608")
      (libsource (lib "eagle-import") (part "R-EU-1608"))
    )
    (comp (ref "R211")
      (value "10k")
      (footprint "eagle-import:R1608")
      (libsource (lib "eagle-import") (part "R-EU-1608"))
    )
    (comp (ref "R212")
      (value "10k")
      (footprint "eagle-import:R1608")
      (libsource (lib "eagle-import") (part "R-EU-1608"))
    )
    (comp (ref "R213")
      (value "10k")
      (footprint "eagle-import:R1608")
      (libsource (lib "eagle-import") (part "R-EU-1608"))
    )
    (comp (ref "R214")
      (value "10k")
      (footprint "eagle-import:R1608")
      (libsource (lib "eagle-import") (part "R-EU-1608"))
    )
    (comp (ref "R215")
      (value "10k")
      (footprint "eagle-import:R1608")
      (libsource (lib "eagle-import") (part "R-EU-1608"))
    )
    (comp (ref "R216")
      (value "10k")
      (footprint "eagle-import:R1608")
      (libsource (lib "eagle-import") (part "R-EU-1608"))
    )
    (comp (ref "R217")
      (value "10k")
      (footprint "eagle-import:R1608")
      (libsource (lib "eagle-import") (part "R-EU-1608"))
    )
    (comp (ref "R218")
      (value "10k")
      (footprint "eagle-import:R1608")
      (libsource (lib "eagle-import") (part "R-EU-1608"))
    )
    (comp (ref "R219")
      (value "10k")
      (footprint "eagle-import:R1608")
      (libsource (lib "eagle-import") (part "R-EU-1608"))
    )
    (comp (ref "R220")
      (value "10k")
      (footprint "eagle-import:R1608")
      (libsource (lib "eagle-import") (part "R-EU-1608"))
    )
    (comp (ref "R221")
      (value "10k")
      (footprint "eagle-import:R1608")
      (libsource (lib "eagle-import") (part "R-EU-1608"))
    )
    (comp (ref "R222")
      (value "10k")
      (footprint "eagle-import:R1608")
      (libsource (lib "eagle-import") (part "R-EU-1608"))
    )
    (comp (ref "R223")
      (value "10k")
      (footprint "eagle-import:R1608")
      (libsource (lib "eagle-import") (part "R-EU-1608"))
    )
    (comp (ref "R224")
      (value "10k")
      (footprint "eagle-import:R1608")
      (libsource (lib "eagle-import") (part "R-EU-1608"))
    )
    (comp (ref "R225")
      (value "10k")
      (footprint "eagle-import:R1608")
      (libsource (lib "eagle-import") (part "R-EU-1608"))
    )
    (comp (ref "R226")
      (value "10k")
      (footprint "eagle-import:R1608")
      (libsource (lib "eagle-import") (part "R-EU-1608"))
    )
    (comp (ref "R227")
      (value "2k15")
      (footprint "eagle-import:R2012W")
      (libsource (lib "eagle-import") (part "R-EU-2012"))
    )
    (comp (ref "R228")
      (value "2k15")
      (footprint "eagle-import:R2012W")
      (libsource (lib "eagle-import") (part "R-EU-2012"))
    )
    (comp (ref "R229")
      (value "100R")
      (footprint "eagle-import:R2012W")
      (libsource (lib "eagle-import") (part "R-EU-2012"))
    )
    (comp (ref "R230")
      (value "100R")
      (footprint "eagle-import:R2012W")
      (libsource (lib "eagle-import") (part "R-EU-2012"))
    )
    (comp (ref "R231")
      (value "1k")
      (footprint "eagle-import:R1608")
      (libsource (lib "eagle-import") (part "R-EU-1608"))
    )
    (comp (ref "R232")
      (value "2R")
      (footprint "eagle-import:R3216W")
      (libsource (lib "eagle-import") (part "R-EU-3216"))
    )
    (comp (ref "R233")
      (value "1k")
      (footprint "eagle-import:R1608")
      (libsource (lib "eagle-import") (part "R-EU-1608"))
    )
    (comp (ref "R234")
      (value "2R")
      (footprint "eagle-import:R3216W")
      (libsource (lib "eagle-import") (part "R-EU-3216"))
    )
    (comp (ref "R235")
      (value "100k")
      (footprint "eagle-import:R1608")
      (libsource (lib "eagle-import") (part "R-EU-1608"))
    )
    (comp (ref "R236")
      (value "100k")
      (footprint "eagle-import:R1608")
      (libsource (lib "eagle-import") (part "R-EU-1608"))
    )
    (comp (ref "R237")
      (value "1k")
      (footprint "eagle-import:R1608")
      (libsource (lib "eagle-import") (part "R-EU-1608"))
    )
    (comp (ref "R238")
      (value "2R")
      (footprint "eagle-import:R3216W")
      (libsource (lib "eagle-import") (part "R-EU-3216"))
    )
    (comp (ref "R239")
      (value "1k")
      (footprint "eagle-import:R1608")
      (libsource (lib "eagle-import") (part "R-EU-1608"))
    )
    (comp (ref "R240")
      (value "2R")
      (footprint "eagle-import:R3216W")
      (libsource (lib "eagle-import") (part "R-EU-3216"))
    )
    (comp (ref "R241")
      (value "0R01")
      (footprint "eagle-import:R6332W")
      (libsource (lib "eagle-import") (part "R-EU-6332"))
    )
    (comp (ref "R242")
      (value "0R01")
      (footprint "eagle-import:R6332W")
      (libsource (lib "eagle-import") (part "R-EU-6332"))
    )
    (comp (ref "R243")
      (value "2R")
      (footprint "eagle-import:R3216W")
      (libsource (lib "eagle-import") (part "R-EU-3216"))
    )
    (comp (ref "R244")
      (value "0R01")
      (footprint "eagle-import:R6332W")
      (libsource (lib "eagle-import") (part "R-EU-6332"))
    )
    (comp (ref "R245")
      (value "2R")
      (footprint "eagle-import:R3216W")
      (libsource (lib "eagle-import") (part "R-EU-3216"))
    )
    (comp (ref "R246")
      (value "0R01")
      (footprint "eagle-import:R6332W")
      (libsource (lib "eagle-import") (part "R-EU-6332"))
    )
    (comp (ref "R247")
      (value "2k15")
      (footprint "eagle-import:R2012W")
      (libsource (lib "eagle-import") (part "R-EU-2012"))
    )
    (comp (ref "R248")
      (value "2k15")
      (footprint "eagle-import:R2012W")
      (libsource (lib "eagle-import") (part "R-EU-2012"))
    )
    (comp (ref "R249")
      (value "0R01")
      (footprint "eagle-import:R6332W")
      (libsource (lib "eagle-import") (part "R-EU-6332"))
    )
    (comp (ref "R250")
      (value "0R01")
      (footprint "eagle-import:R6332W")
      (libsource (lib "eagle-import") (part "R-EU-6332"))
    )
    (comp (ref "R251")
      (value "2k15")
      (footprint "eagle-import:R2012W")
      (libsource (lib "eagle-import") (part "R-EU-2012"))
    )
    (comp (ref "R252")
      (value "2k15")
      (footprint "eagle-import:R2012W")
      (libsource (lib "eagle-import") (part "R-EU-2012"))
    )
    (comp (ref "R253")
      (value "2k15")
      (footprint "eagle-import:R2012W")
      (libsource (lib "eagle-import") (part "R-EU-2012"))
    )
    (comp (ref "R254")
      (value "2k15")
      (footprint "eagle-import:R2012W")
      (libsource (lib "eagle-import") (part "R-EU-2012"))
    )
    (comp (ref "R255")
      (value "100R")
      (footprint "eagle-import:R2012W")
      (libsource (lib "eagle-import") (part "R-EU-2012"))
    )
    (comp (ref "R256")
      (value "100R")
      (footprint "eagle-import:R2012W")
      (libsource (lib "eagle-import") (part "R-EU-2012"))
    )
    (comp (ref "R257")
      (value "100R")
      (footprint "eagle-import:R2012W")
      (libsource (lib "eagle-import") (part "R-EU-2012"))
    )
    (comp (ref "R258")
      (value "100R")
      (footprint "eagle-import:R2012W")
      (libsource (lib "eagle-import") (part "R-EU-2012"))
    )
    (comp (ref "U201")
      (value "AD420")
      (footprint "eagle-import:SO24W")
      (libsource (lib "eagle-import") (part "AD420RW-24"))
    )
    (comp (ref "U202")
      (value "AD420")
      (footprint "eagle-import:SO24W")
      (libsource (lib "eagle-import") (part "AD420RW-24"))
    )
    (comp (ref "U203")
      (value "LT1014I")
      (footprint "eagle-import:SO16W")
      (libsource (lib "eagle-import") (part "LT1014ISW"))
    )
    (comp (ref "U204")
      (value "LT1014I")
      (footprint "eagle-import:SO16W")
      (libsource (lib "eagle-import") (part "LT1014ISW"))
    )
    (comp (ref "U205")
      (value "AD620")
      (footprint "eagle-import:SO8")
      (libsource (lib "eagle-import") (part "AD620R-8"))
    )
    (comp (ref "U206")
      (value "AD620")
      (footprint "eagle-import:SO8")
      (libsource (lib "eagle-import") (part "AD620R-8"))
    )
    (comp (ref "U207")
      (value "AD620")
      (footprint "eagle-import:SO8")
      (libsource (lib "eagle-import") (part "AD620R-8"))
    )
    (comp (ref "U208")
      (value "AD620")
      (footprint "eagle-import:SO8")
      (libsource (lib "eagle-import") (part "AD620R-8"))
    )
    (comp (ref "U209")
      (value "LTC1865L")
      (footprint "eagle-import:SO8")
      (libsource (lib "eagle-import") (part "LTC1865L"))
    )
    (comp (ref "U210")
      (value "LTC1865L")
      (footprint "eagle-import:SO8")
      (libsource (lib "eagle-import") (part "LTC1865L"))
    )
  )
  (nets
    (net (code "1") (name "+3V3") (class "Default")
      (node (ref "C229") (pin "+") (pinfunction "+_+") (pintype "passive"))
      (node (ref "C230") (pin "+") (pinfunction "+_+") (pintype "passive"))
      (node (ref "C231") (pin "1") (pinfunction "1_1") (pintype "passive"))
      (node (ref "C232") (pin "1") (pinfunction "1_1") (pintype "passive"))
      (node (ref "C315") (pin "1") (pinfunction "1_1") (pintype "passive"))
      (node (ref "C321") (pin "+") (pinfunction "+_+") (pintype "passive"))
      (node (ref "C322") (pin "1") (pinfunction "1_1") (pintype "passive"))
      (node (ref "C326") (pin "+") (pinfunction "+_+") (pintype "passive"))
      (node (ref "C327") (pin "1") (pinfunction "1_1") (pintype "passive"))
      (node (ref "D201") (pin "2") (pinfunction "C2_2") (pintype "passive"))
      (node (ref "D202") (pin "2") (pinfunction "C2_2") (pintype "passive"))
      (node (ref "D203") (pin "2") (pinfunction "C2_2") (pintype "passive"))
      (node (ref "D204") (pin "2") (pinfunction "C2_2") (pintype "passive"))
      (node (ref "D303") (pin "2") (pinfunction "C2_2") (pintype "passive"))
      (node (ref "R412") (pin "2") (pinfunction "2_2") (pintype "passive"))
      (node (ref "R413") (pin "2") (pinfunction "2_2") (pintype "passive"))
      (node (ref "R414") (pin "2") (pinfunction "2_2") (pintype "passive"))
      (node (ref "R416") (pin "2") (pinfunction "2_2") (pintype "passive"))
      (node (ref "R426") (pin "2") (pinfunction "2_2") (pintype "passive"))
      (node (ref "R427") (pin "2") (pinfunction "2_2") (pintype "passive"))
      (node (ref "U209") (pin "8") (pinfunction "VCC_8") (pintype "power_in"))
      (node (ref "U210") (pin "8") (pinfunction "VCC_8") (pintype "power_in"))
      (node (ref "U302") (pin "5") (pinfunction "VOUT_5") (pintype "power_in"))
      (node (ref "U306") (pin "8") (pinfunction "VCC_8") (pintype "power_in"))
      (node (ref "U307") (pin "8") (pinfunction "VCC_8") (pintype "power_in"))
    )
    (net (code "2") (name "+5V") (class "Default")
      (node (ref "C209") (pin "+") (pinfunction "+_+") (pintype "passive"))
      (node (ref "C210") (pin "+") (pinfunction "+_+") (pintype "passive"))
      (node (ref "C211") (pin "1") (pinfunction "1_1") (pintype "passive"))
      (node (ref "C212") (pin "1") (pinfunction "1_1") (pintype "passive"))
      (node (ref "C303") (pin "2") (pinfunction "2_2") (pintype "passive"))
      (node (ref "C308") (pin "1") (pinfunction "1_1") (pintype "passive"))
      (node (ref "C309") (pin "1") (pinfunction "1_1") (pintype "passive"))
      (node (ref "C310") (pin "+") (pinfunction "+_+") (pintype "passive"))
      (node (ref "C316") (pin "1") (pinfunction "1_1") (pintype "passive"))
      (node (ref "C317") (pin "1") (pinfunction "1_1") (pintype "passive"))
      (node (ref "C401") (pin "1") (pinfunction "1_1") (pintype "passive"))
      (node (ref "C402") (pin "1") (pinfunction "1_1") (pintype "passive"))
      (node (ref "C403") (pin "1") (pinfunction "1_1") (pintype "passive"))
      (node (ref "C404") (pin "1") (pinfunction "1_1") (pintype "passive"))
      (node (ref "C405") (pin "1") (pinfunction "1_1") (pintype "passive"))
      (node (ref "C406") (pin "1") (pinfunction "1_1") (pintype "passive"))
      (node (ref "C407") (pin "1") (pinfunction "1_1") (pintype "passive"))
      (node (ref "C408") (pin "1") (pinfunction "1_1") (pintype "passive"))
      (node (ref "C417") (pin "1") (pinfunction "1_1") (pintype "passive"))
      (node (ref "C418") (pin "1") (pinfunction "1_1") (pintype "passive"))
      (node (ref "C420") (pin "1") (pinfunction "1_1") (pintype "passive"))
      (node (ref "C421") (pin "1") (pinfunction "1_1") (pintype "passive"))
      (node (ref "IC301") (pin "3") (pinfunction "VO_3") (pintype "passive"))
      (node (ref "IC302") (pin "3") (pinfunction "VO_3") (pintype "passive"))
      (node (ref "L302") (pin "1") (pinfunction "1_1") (pintype "passive"))
      (node (ref "PS301") (pin "1") (pinfunction "+VI_1") (pintype "power_in"))
      (node (ref "R409") (pin "2") (pinfunction "2_2") (pintype "passive"))
      (node (ref "R410") (pin "2") (pinfunction "2_2") (pintype "passive"))
      (node (ref "R411") (pin "2") (pinfunction "2_2") (pintype "passive"))
      (node (ref "R415") (pin "2") (pinfunction "2_2") (pintype "passive"))
      (node (ref "R419") (pin "2") (pinfunction "2_2") (pintype "passive"))
      (node (ref "R422") (pin "2") (pinfunction "2_2") (pintype "passive"))
      (node (ref "R423") (pin "2") (pinfunction "2_2") (pintype "passive"))
      (node (ref "R424") (pin "2") (pinfunction "2_2") (pintype "passive"))
      (node (ref "U201") (pin "2") (pinfunction "VLL_2") (pintype "bidirectional"))
      (node (ref "U202") (pin "2") (pinfunction "VLL_2") (pintype "bidirectional"))
      (node (ref "U301") (pin "12") (pinfunction "V+_12") (pintype "input"))
      (node (ref "U301") (pin "13") (pinfunction "V+_13") (pintype "input"))
      (node (ref "U301") (pin "3") (pinfunction "AV+_3") (pintype "input"))
      (node (ref "U301") (pin "4") (pinfunction "V+_4") (pintype "input"))
      (node (ref "U301") (pin "5") (pinfunction "V+_5") (pintype "input"))
      (node (ref "U303") (pin "1") (pinfunction "+V_1") (pintype "power_in"))
      (node (ref "U304") (pin "1") (pinfunction "+V_1") (pintype "power_in"))
      (node (ref "U401") (pin "8") (pinfunction "VCC_8") (pintype "power_in"))
      (node (ref "U402") (pin "8") (pinfunction "VCC_8") (pintype "power_in"))
      (node (ref "U403") (pin "8") (pinfunction "VCC_8") (pintype "power_in"))
      (node (ref "U404") (pin "8") (pinfunction "VCC_8") (pintype "power_in"))
      (node (ref "U405") (pin "8") (pinfunction "VCC_8") (pintype "power_in"))
      (node (ref "U406") (pin "8") (pinfunction "VCC_8") (pintype "power_in"))
    )
    (net (code "3") (name "+5V_I") (class "Default")
      (node (ref "C419") (pin "1") (pinfunction "1_1") (pintype "passive"))
      (node (ref "C422") (pin "1") (pinfunction "1_1") (pintype "passive"))
      (node (ref "PS301") (pin "7") (pinfunction "+VO_7") (pintype "power_in"))
      (node (ref "R401") (pin "2") (pinfunction "2_2") (pintype "passive"))
      (node (ref "R402") (pin "2") (pinfunction "2_2") (pintype "passive"))
      (node (ref "R403") (pin "2") (pinfunction "2_2") (pintype "passive"))
      (node (ref "R404") (pin "2") (pinfunction "2_2") (pintype "passive"))
      (node (ref "R405") (pin "2") (pinfunction "2_2") (pintype "passive"))
      (node (ref "R406") (pin "2") (pinfunction "2_2") (pintype "passive"))
      (node (ref "R407") (pin "2") (pinfunction "2_2") (pintype "passive"))
      (node (ref "R408") (pin "2") (pinfunction "2_2") (pintype "passive"))
      (node (ref "R417") (pin "2") (pinfunction "2_2") (pintype "passive"))
      (node (ref "R418") (pin "2") (pinfunction "2_2") (pintype "passive"))
      (node (ref "R420") (pin "2") (pinfunction "2_2") (pintype "passive"))
      (node (ref "R421") (pin "2") (pinfunction "2_2") (pintype "passive"))
      (node (ref "R425") (pin "2") (pinfunction "2_2") (pintype "passive"))
      (node (ref "R428") (pin "2") (pinfunction "2_2") (pintype "passive"))
      (node (ref "U407") (pin "8") (pinfunction "VCC_8") (pintype "power_in"))
    )
    (net (code "4") (name "+12V") (class "Default")
      (node (ref "C205") (pin "1") (pinfunction "1_1") (pintype "passive"))
      (node (ref "C206") (pin "1") (pinfunction "1_1") (pintype "passive"))
      (node (ref "C207") (pin "1") (pinfunction "1_1") (pintype "passive"))
      (node (ref "C208") (pin "1") (pinfunction "1_1") (pintype "passive"))
      (node (ref "C213") (pin "1") (pinfunction "1_1") (pintype "passive"))
      (node (ref "C214") (pin "1") (pinfunction "1_1") (pintype "passive"))
      (node (ref "C215") (pin "1") (pinfunction "1_1") (pintype "passive"))
      (node (ref "C216") (pin "1") (pinfunction "1_1") (pintype "passive"))
      (node (ref "C301") (pin "1") (pinfunction "1_1") (pintype "passive"))
      (node (ref "C302") (pin "1") (pinfunction "1_1") (pintype "passive"))
      (node (ref "IC301") (pin "1") (pinfunction "VI_1") (pintype "input"))
      (node (ref "IC302") (pin "1") (pinfunction "VI_1") (pintype "input"))
      (node (ref "J301") (pin "3") (pinfunction "3_3") (pintype "passive"))
      (node (ref "J302") (pin "2") (pinfunction "+12V_2") (pintype "passive"))
      (node (ref "J303") (pin "2") (pinfunction "+12V_2") (pintype "passive"))
      (node (ref "Q207") (pin "3") (pinfunction "C_3") (pintype "passive"))
      (node (ref "Q209") (pin "3") (pinfunction "C_3") (pintype "passive"))
      (node (ref "R235") (pin "2") (pinfunction "2_2") (pintype "passive"))
      (node (ref "R236") (pin "2") (pinfunction "2_2") (pintype "passive"))
      (node (ref "R237") (pin "2") (pinfunction "2_2") (pintype "passive"))
      (node (ref "R239") (pin "2") (pinfunction "2_2") (pintype "passive"))
      (node (ref "U201") (pin "23") (pinfunction "VCC_23") (pintype "bidirectional"))
      (node (ref "U202") (pin "23") (pinfunction "VCC_23") (pintype "bidirectional"))
    )
    (net (code "5") (name "+15V") (class "Default")
      (node (ref "C201") (pin "1") (pinfunction "1_1") (pintype "passive"))
      (node (ref "C202") (pin "1") (pinfunction "1_1") (pintype "passive"))
      (node (ref "C217") (pin "1") (pinfunction "1_1") (pintype "passive"))
      (node (ref "C218") (pin "1") (pinfunction "1_1") (pintype "passive"))
      (node (ref "C219") (pin "1") (pinfunction "1_1") (pintype "passive"))
      (node (ref "C220") (pin "1") (pinfunction "1_1") (pintype "passive"))
      (node (ref "C311") (pin "+") (pinfunction "+_+") (pintype "passive"))
      (node (ref "C323") (pin "1") (pinfunction "1_1") (pintype "passive"))
      (node (ref "D301") (pin "C") (pinfunction "C_C") (pintype "passive"))
      (node (ref "U203") (pin "4") (pinfunction "V+_4") (pintype "power_in"))
      (node (ref "U204") (pin "4") (pinfunction "V+_4") (pintype "power_in"))
      (node (ref "U205") (pin "7") (pinfunction "+V_7") (pintype "power_in"))
      (node (ref "U206") (pin "7") (pinfunction "+V_7") (pintype "power_in"))
      (node (ref "U207") (pin "7") (pinfunction "+V_7") (pintype "power_in"))
      (node (ref "U208") (pin "7") (pinfunction "+V_7") (pintype "power_in"))
      (node (ref "U301") (pin "16") (pinfunction "FB+_16") (pintype "input"))
      (node (ref "U305") (pin "7") (pinfunction "+V_7") (pintype "power_in"))
    )
    (net (code "6") (name "-15V") (class "Default")
      (node (ref "C203") (pin "1") (pinfunction "1_1") (pintype "passive"))
      (node (ref "C204") (pin "1") (pinfunction "1_1") (pintype "passive"))
      (node (ref "C221") (pin "1") (pinfunction "1_1") (pintype "passive"))
      (node (ref "C222") (pin "1") (pinfunction "1_1") (pintype "passive"))
      (node (ref "C223") (pin "1") (pinfunction "1_1") (pintype "passive"))
      (node (ref "C224") (pin "1") (pinfunction "1_1") (pintype "passive"))
      (node (ref "C312") (pin "-") (pinfunction "-_-") (pintype "passive"))
      (node (ref "C325") (pin "1") (pinfunction "1_1") (pintype "passive"))
      (node (ref "D302") (pin "A") (pinfunction "A_A") (pintype "passive"))
      (node (ref "U203") (pin "13") (pinfunction "V-_13") (pintype "power_in"))
      (node (ref "U204") (pin "13") (pinfunction "V-_13") (pintype "power_in"))
      (node (ref "U205") (pin "4") (pinfunction "-V_4") (pintype "power_in"))
      (node (ref "U206") (pin "4") (pinfunction "-V_4") (pintype "power_in"))
      (node (ref "U207") (pin "4") (pinfunction "-V_4") (pintype "power_in"))
      (node (ref "U208") (pin "4") (pinfunction "-V_4") (pintype "power_in"))
      (node (ref "U301") (pin "9") (pinfunction "FB-_9") (pintype "input"))
      (node (ref "U305") (pin "4") (pinfunction "-V_4") (pintype "power_in"))
    )
    (net (code "7") (name "BYP") (class "Default")
      (node (ref "C409") (pin "1") (pinfunction "1_1") (pintype "passive"))
      (node (ref "R231") (pin "1") (pinfunction "1_1") (pintype "passive"))
      (node (ref "R233") (pin "1") (pinfunction "1_1") (pintype "passive"))
      (node (ref "R409") (pin "1") (pinfunction "1_1") (pintype "passive"))
      (node (ref "U401") (pin "7") (pinfunction "VO1_7") (pintype "output"))
    )
    (net (code "8") (name "BYP1") (class "Default")
      (node (ref "Q209") (pin "2") (pinfunction "E_2") (pintype "passive"))
      (node (ref "Q210") (pin "2") (pinfunction "E_2") (pintype "passive"))
      (node (ref "R232") (pin "1") (pinfunction "1_1") (pintype "passive"))
      (node (ref "R238") (pin "1") (pinfunction "1_1") (pintype "passive"))
      (node (ref "R248") (pin "1") (pinfunction "1_1") (pintype "passive"))
    )
    (net (code "9") (name "BYP2") (class "Default")
      (node (ref "Q207") (pin "2") (pinfunction "E_2") (pintype "passive"))
      (node (ref "Q208") (pin "2") (pinfunction "E_2") (pintype "passive"))
      (node (ref "R234") (pin "1") (pinfunction "1_1") (pintype "passive"))
      (node (ref "R240") (pin "1") (pinfunction "1_1") (pintype "passive"))
      (node (ref "R247") (pin "2") (pinfunction "2_2") (pintype "passive"))
    )
    (net (code "10") (name "BYP_I") (class "Default")
      (node (ref "Q401") (pin "1") (pinfunction "B_1") (pintype "passive"))
    )
    (net (code "11") (name "CLR_DAC1") (class "Default")
      (node (ref "C424") (pin "1") (pinfunction "1_1") (pintype "passive"))
      (node (ref "R424") (pin "1") (pinfunction "1_1") (pintype "passive"))
      (node (ref "U201") (pin "6") (pinfunction "CLR_6") (pintype "bidirectional"))
      (node (ref "U406") (pin "7") (pinfunction "VO1_7") (pintype "output"))
    )
    (net (code "12") (name "CLR_DAC1_I") (class "Default")
      (node (ref "Q410") (pin "1") (pinfunction "B_1") (pintype "passive"))
    )
    (net (code "13") (name "CLR_DAC2") (class "Default")
      (node (ref "C427") (pin "1") (pinfunction "1_1") (pintype "passive"))
      (node (ref "R427") (pin "1") (pinfunction "1_1") (pintype "passive"))
      (node (ref "U202") (pin "6") (pinfunction "CLR_6") (pintype "bidirectional"))
      (node (ref "U406") (pin "6") (pinfunction "VO2_6") (pintype "output"))
    )
    (net (code "14") (name "CLR_DAC2_I") (class "Default")
      (node (ref "Q413") (pin "1") (pinfunction "B_1") (pintype "passive"))
    )
    (net (code "15") (name "CONV_C1") (class "Default")
      (node (ref "C411") (pin "1") (pinfunction "1_1") (pintype "passive"))
      (node (ref "R411") (pin "1") (pinfunction "1_1") (pintype "passive"))
      (node (ref "U209") (pin "1") (pinfunction "CONV_1") (pintype "input"))
      (node (ref "U403") (pin "7") (pinfunction "VO1_7") (pintype "output"))
    )
    (net (code "16") (name "CONV_C1_I") (class "Default")
      (node (ref "Q403") (pin "1") (pinfunction "B_1") (pintype "passive"))
    )
    (net (code "17") (name "CONV_C2") (class "Default")
      (node (ref "C415") (pin "1") (pinfunction "1_1") (pintype "passive"))
      (node (ref "R415") (pin "1") (pinfunction "1_1") (pintype "passive"))
      (node (ref "U210") (pin "1") (pinfunction "CONV_1") (pintype "input"))
      (node (ref "U403") (pin "6") (pinfunction "VO2_6") (pintype "output"))
    )
    (net (code "18") (name "CONV_C2_I") (class "Default")
      (node (ref "Q407") (pin "1") (pinfunction "B_1") (pintype "passive"))
    )
    (net (code "19") (name "CONV_TEMP") (class "Default")
      (node (ref "C410") (pin "1") (pinfunction "1_1") (pintype "passive"))
      (node (ref "R410") (pin "1") (pinfunction "1_1") (pintype "passive"))
      (node (ref "U306") (pin "1") (pinfunction "CONV_1") (pintype "input"))
      (node (ref "U402") (pin "7") (pinfunction "VO1_7") (pintype "output"))
    )
    (net (code "20") (name "CONV_TEMP_I") (class "Default")
      (node (ref "Q402") (pin "1") (pinfunction "B_1") (pintype "passive"))
    )
    (net (code "21") (name "CONV_V") (class "Default")
      (node (ref "C414") (pin "1") (pinfunction "1_1") (pintype "passive"))
      (node (ref "R414") (pin "1") (pinfunction "1_1") (pintype "passive"))
      (node (ref "U307") (pin "1") (pinfunction "CONV_1") (pintype "input"))
      (node (ref "U402") (pin "6") (pinfunction "VO2_6") (pintype "output"))
    )
    (net (code "22") (name "CONV_V_I") (class "Default")
      (node (ref "Q406") (pin "1") (pinfunction "B_1") (pintype "passive"))
    )
    (net (code "23") (name "CSEN_H1") (class "Default")
      (node (ref "Q201") (pin "1") (pinfunction "S_1") (pintype "passive"))
      (node (ref "Q201") (pin "2") (pinfunction "S_2") (pintype "passive"))
      (node (ref "Q201") (pin "3") (pinfunction "S_3") (pintype "passive"))
      (node (ref "Q205") (pin "1") (pinfunction "S_1") (pintype "passive"))
      (node (ref "Q205") (pin "2") (pinfunction "S_2") (pintype "passive"))
      (node (ref "Q205") (pin "3") (pinfunction "S_3") (pintype "passive"))
      (node (ref "R241") (pin "2") (pinfunction "2_2") (pintype "passive"))
      (node (ref "R243") (pin "1") (pinfunction "1_1") (pintype "passive"))
      (node (ref "R244") (pin "2") (pinfunction "2_2") (pintype "passive"))
      (node (ref "R248") (pin "2") (pinfunction "2_2") (pintype "passive"))
      (node (ref "R249") (pin "2") (pinfunction "2_2") (pintype "passive"))
      (node (ref "U205") (pin "3") (pinfunction "+_3") (pintype "input"))
      (node (ref "U206") (pin "2") (pinfunction "-_2") (pintype "input"))
    )
    (net (code "24") (name "CSEN_H2") (class "Default")
      (node (ref "Q202") (pin "1") (pinfunction "S_1") (pintype "passive"))
      (node (ref "Q202") (pin "2") (pinfunction "S_2") (pintype "passive"))
      (node (ref "Q202") (pin "3") (pinfunction "S_3") (pintype "passive"))
      (node (ref "Q206") (pin "1") (pinfunction "S_1") (pintype "passive"))
      (node (ref "Q206") (pin "2") (pinfunction "S_2") (pintype "passive"))
      (node (ref "Q206") (pin "3") (pinfunction "S_3") (pintype "passive"))
      (node (ref "R242") (pin "2") (pinfunction "2_2") (pintype "passive"))
      (node (ref "R245") (pin "1") (pinfunction "1_1") (pintype "passive"))
      (node (ref "R246") (pin "2") (pinfunction "2_2") (pintype "passive"))
      (node (ref "R247") (pin "1") (pinfunction "1_1") (pintype "passive"))
      (node (ref "R250") (pin "2") (pinfunction "2_2") (pintype "passive"))
      (node (ref "U207") (pin "3") (pinfunction "+_3") (pintype "input"))
      (node (ref "U208") (pin "2") (pinfunction "-_2") (pintype "input"))
    )
    (net (code "25") (name "CSEN_L1") (class "Default")
      (node (ref "Q201") (pin "5") (pinfunction "D_5") (pintype "passive"))
      (node (ref "Q205") (pin "5") (pinfunction "D_5") (pintype "passive"))
      (node (ref "Q211") (pin "1") (pinfunction "S_1") (pintype "passive"))
      (node (ref "R201") (pin "1") (pinfunction "1_1") (pintype "passive"))
      (node (ref "R227") (pin "1") (pinfunction "1_1") (pintype "passive"))
      (node (ref "R243") (pin "2") (pinfunction "2_2") (pintype "passive"))
      (node (ref "U206") (pin "3") (pinfunction "+_3") (pintype "input"))
    )
    (net (code "26") (name "CSEN_L2") (class "Default")
      (node (ref "Q202") (pin "5") (pinfunction "D_5") (pintype "passive"))
      (node (ref "Q206") (pin "5") (pinfunction "D_5") (pintype "passive"))
      (node (ref "Q212") (pin "1") (pinfunction "S_1") (pintype "passive"))
      (node (ref "R202") (pin "1") (pinfunction "1_1") (pintype "passive"))
      (node (ref "R228") (pin "1") (pinfunction "1_1") (pintype "passive"))
      (node (ref "R245") (pin "2") (pinfunction "2_2") (pintype "passive"))
      (node (ref "U208") (pin "3") (pinfunction "+_3") (pintype "input"))
    )
    (net (code "27") (name "DUT+") (class "Default")
      (node (ref "Q211") (pin "2") (pinfunction "D_2") (pintype "passive"))
      (node (ref "Q212") (pin "2") (pinfunction "D_2") (pintype "passive"))
      (node (ref "R303") (pin "2") (pinfunction "2_2") (pintype "passive"))
      (node (ref "X301") (pin "2") (pinfunction "1_2") (pintype "passive"))
    )
    (net (code "28") (name "DUT-") (class "Default")
      (node (ref "C320") (pin "2") (pinfunction "2_2") (pintype "passive"))
      (node (ref "R203") (pin "1") (pinfunction "1_1") (pintype "passive"))
      (node (ref "R204") (pin "1") (pinfunction "1_1") (pintype "passive"))
      (node (ref "R241") (pin "1") (pinfunction "1_1") (pintype "passive"))
      (node (ref "R242") (pin "1") (pinfunction "1_1") (pintype "passive"))
      (node (ref "R244") (pin "1") (pinfunction "1_1") (pintype "passive"))
      (node (ref "R246") (pin "1") (pinfunction "1_1") (pintype "passive"))
      (node (ref "R249") (pin "1") (pinfunction "1_1") (pintype "passive"))
      (node (ref "R250") (pin "1") (pinfunction "1_1") (pintype "passive"))
      (node (ref "R301") (pin "2") (pinfunction "2_2") (pintype "passive"))
      (node (ref "U205") (pin "2") (pinfunction "-_2") (pintype "input"))
      (node (ref "U207") (pin "2") (pinfunction "-_2") (pintype "input"))
      (node (ref "X301") (pin "3") (pinfunction "1_3") (pintype "passive"))
    )
    (net (code "29") (name "FAN1_PWM") (class "Default")
      (node (ref "C423") (pin "1") (pinfunction "1_1") (pintype "passive"))
      (node (ref "J302") (pin "4") (pinfunction "PWM_4") (pintype "passive"))
      (node (ref "R423") (pin "1") (pinfunction "1_1") (pintype "passive"))
      (node (ref "U405") (pin "7") (pinfunction "VO1_7") (pintype "output"))
    )
    (net (code "30") (name "FAN1_PWM_I") (class "Default")
      (node (ref "Q409") (pin "1") (pinfunction "B_1") (pintype "passive"))
    )
    (net (code "31") (name "FAN1_SIG") (class "Default")
      (node (ref "J302") (pin "3") (pinfunction "SIG_3") (pintype "passive"))
    )
    (net (code "32") (name "FAN2_PWM") (class "Default")
      (node (ref "C426") (pin "1") (pinfunction "1_1") (pintype "passive"))
      (node (ref "J303") (pin "4") (pinfunction "PWM_4") (pintype "passive"))
      (node (ref "R426") (pin "1") (pinfunction "1_1") (pintype "passive"))
      (node (ref "U405") (pin "6") (pinfunction "VO2_6") (pintype "output"))
    )
    (net (code "33") (name "FAN2_PWM_I") (class "Default")
      (node (ref "Q412") (pin "1") (pinfunction "B_1") (pintype "passive"))
    )
    (net (code "34") (name "FAN2_SIG") (class "Default")
      (node (ref "J303") (pin "3") (pinfunction "SIG_3") (pintype "passive"))
    )
    (net (code "35") (name "FLT_DAC") (class "Default")
      (node (ref "Q414") (pin "1") (pinfunction "B_1") (pintype "passive"))
      (node (ref "U201") (pin "3") (pinfunction "FLT_3") (pintype "bidirectional"))
      (node (ref "U202") (pin "3") (pinfunction "FLT_3") (pintype "bidirectional"))
    )
    (net (code "36") (name "FLT_DAC_I") (class "Default")
      (node (ref "C428") (pin "1") (pinfunction "1_1") (pintype "passive"))
      (node (ref "R428") (pin "1") (pinfunction "1_1") (pintype "passive"))
      (node (ref "U407") (pin "6") (pinfunction "VO2_6") (pintype "output"))
    )
    (net (code "37") (name "GND") (class "Default")
      (node (ref "C201") (pin "2") (pinfunction "2_2") (pintype "passive"))
      (node (ref "C202") (pin "2") (pinfunction "2_2") (pintype "passive"))
      (node (ref "C203") (pin "2") (pinfunction "2_2") (pintype "passive"))
      (node (ref "C204") (pin "2") (pinfunction "2_2") (pintype "passive"))
      (node (ref "C209") (pin "-") (pinfunction "-_-") (pintype "passive"))
      (node (ref "C210") (pin "-") (pinfunction "-_-") (pintype "passive"))
      (node (ref "C211") (pin "2") (pinfunction "2_2") (pintype "passive"))
      (node (ref "C212") (pin "2") (pinfunction "2_2") (pintype "passive"))
      (node (ref "C213") (pin "2") (pinfunction "2_2") (pintype "passive"))
      (node (ref "C214") (pin "2") (pinfunction "2_2") (pintype "passive"))
      (node (ref "C215") (pin "2") (pinfunction "2_2") (pintype "passive"))
      (node (ref "C216") (pin "2") (pinfunction "2_2") (pintype "passive"))
      (node (ref "C217") (pin "2") (pinfunction "2_2") (pintype "passive"))
      (node (ref "C218") (pin "2") (pinfunction "2_2") (pintype "passive"))
      (node (ref "C219") (pin "2") (pinfunction "2_2") (pintype "passive"))
      (node (ref "C220") (pin "2") (pinfunction "2_2") (pintype "passive"))
      (node (ref "C221") (pin "2") (pinfunction "2_2") (pintype "passive"))
      (node (ref "C222") (pin "2") (pinfunction "2_2") (pintype "passive"))
      (node (ref "C223") (pin "2") (pinfunction "2_2") (pintype "passive"))
      (node (ref "C224") (pin "2") (pinfunction "2_2") (pintype "passive"))
      (node (ref "C225") (pin "2") (pinfunction "2_2") (pintype "passive"))
      (node (ref "C226") (pin "2") (pinfunction "2_2") (pintype "passive"))
      (node (ref "C227") (pin "2") (pinfunction "2_2") (pintype "passive"))
      (node (ref "C228") (pin "2") (pinfunction "2_2") (pintype "passive"))
      (node (ref "C229") (pin "-") (pinfunction "-_-") (pintype "passive"))
      (node (ref "C230") (pin "-") (pinfunction "-_-") (pintype "passive"))
      (node (ref "C231") (pin "2") (pinfunction "2_2") (pintype "passive"))
      (node (ref "C232") (pin "2") (pinfunction "2_2") (pintype "passive"))
      (node (ref "C301") (pin "2") (pinfunction "2_2") (pintype "passive"))
      (node (ref "C302") (pin "2") (pinfunction "2_2") (pintype "passive"))
      (node (ref "C303") (pin "1") (pinfunction "1_1") (pintype "passive"))
      (node (ref "C304") (pin "-") (pinfunction "-_-") (pintype "passive"))
      (node (ref "C305") (pin "1") (pinfunction "1_1") (pintype "passive"))
      (node (ref "C306") (pin "-") (pinfunction "-_-") (pintype "passive"))
      (node (ref "C307") (pin "2") (pinfunction "2_2") (pintype "passive"))
      (node (ref "C308") (pin "2") (pinfunction "2_2") (pintype "passive"))
      (node (ref "C309") (pin "2") (pinfunction "2_2") (pintype "passive"))
      (node (ref "C310") (pin "-") (pinfunction "-_-") (pintype "passive"))
      (node (ref "C311") (pin "-") (pinfunction "-_-") (pintype "passive"))
      (node (ref "C312") (pin "+") (pinfunction "+_+") (pintype "passive"))
      (node (ref "C313") (pin "2") (pinfunction "2_2") (pintype "passive"))
      (node (ref "C314") (pin "2") (pinfunction "2_2") (pintype "passive"))
      (node (ref "C315") (pin "2") (pinfunction "2_2") (pintype "passive"))
      (node (ref "C316") (pin "2") (pinfunction "2_2") (pintype "passive"))
      (node (ref "C317") (pin "2") (pinfunction "2_2") (pintype "passive"))
      (node (ref "C318") (pin "-") (pinfunction "-_-") (pintype "passive"))
      (node (ref "C319") (pin "-") (pinfunction "-_-") (pintype "passive"))
      (node (ref "C321") (pin "-") (pinfunction "-_-") (pintype "passive"))
      (node (ref "C322") (pin "2") (pinfunction "2_2") (pintype "passive"))
      (node (ref "C323") (pin "2") (pinfunction "2_2") (pintype "passive"))
      (node (ref "C324") (pin "2") (pinfunction "2_2") (pintype "passive"))
      (node (ref "C325") (pin "2") (pinfunction "2_2") (pintype "passive"))
      (node (ref "C326") (pin "-") (pinfunction "-_-") (pintype "passive"))
      (node (ref "C327") (pin "2") (pinfunction "2_2") (pintype "passive"))
      (node (ref "C401") (pin "2") (pinfunction "2_2") (pintype "passive"))
      (node (ref "C402") (pin "2") (pinfunction "2_2") (pintype "passive"))
      (node (ref "C403") (pin "2") (pinfunction "2_2") (pintype "passive"))
      (node (ref "C404") (pin "2") (pinfunction "2_2") (pintype "passive"))
      (node (ref "C405") (pin "2") (pinfunction "2_2") (pintype "passive"))
      (node (ref "C406") (pin "2") (pinfunction "2_2") (pintype "passive"))
      (node (ref "C407") (pin "2") (pinfunction "2_2") (pintype "passive"))
      (node (ref "C408") (pin "2") (pinfunction "2_2") (pintype "passive"))
      (node (ref "C409") (pin "2") (pinfunction "2_2") (pintype "passive"))
      (node (ref "C410") (pin "2") (pinfunction "2_2") (pintype "passive"))
      (node (ref "C411") (pin "2") (pinfunction "2_2") (pintype "passive"))
      (node (ref "C412") (pin "2") (pinfunction "2_2") (pintype "passive"))
      (node (ref "C413") (pin "2") (pinfunction "2_2") (pintype "passive"))
      (node (ref "C414") (pin "2") (pinfunction "2_2") (pintype "passive"))
      (node (ref "C415") (pin "2") (pinfunction "2_2") (pintype "passive"))
      (node (ref "C416") (pin "2") (pinfunction "2_2") (pintype "passive"))
      (node (ref "C417") (pin "2") (pinfunction "2_2") (pintype "passive"))
      (node (ref "C418") (pin "2") (pinfunction "2_2") (pintype "passive"))
      (node (ref "C420") (pin "2") (pinfunction "2_2") (pintype "passive"))
      (node (ref "C421") (pin "2") (pinfunction "2_2") (pintype "passive"))
      (node (ref "C423") (pin "2") (pinfunction "2_2") (pintype "passive"))
      (node (ref "C424") (pin "2") (pinfunction "2_2") (pintype "passive"))
      (node (ref "C426") (pin "2") (pinfunction "2_2") (pintype "passive"))
      (node (ref "C427") (pin "2") (pinfunction "2_2") (pintype "passive"))
      (node (ref "D201") (pin "1") (pinfunction "A1_1") (pintype "passive"))
      (node (ref "D202") (pin "1") (pinfunction "A1_1") (pintype "passive"))
      (node (ref "D203") (pin "1") (pinfunction "A1_1") (pintype "passive"))
      (node (ref "D204") (pin "1") (pinfunction "A1_1") (pintype "passive"))
      (node (ref "D303") (pin "1") (pinfunction "A1_1") (pintype "passive"))
      (node (ref "IC301") (pin "2") (pinfunction "GND_2") (pintype "passive"))
      (node (ref "IC302") (pin "2") (pinfunction "GND_2") (pintype "passive"))
      (node (ref "J301") (pin "1") (pinfunction "1_1") (pintype "passive"))
      (node (ref "J302") (pin "1") (pinfunction "GND_1") (pintype "passive"))
      (node (ref "J303") (pin "1") (pinfunction "GND_1") (pintype "passive"))
      (node (ref "L301") (pin "2") (pinfunction "2_2") (pintype "passive"))
      (node (ref "PS301") (pin "2") (pinfunction "-VI_2") (pintype "power_in"))
      (node (ref "Q203") (pin "2") (pinfunction "E_2") (pintype "passive"))
      (node (ref "Q204") (pin "2") (pinfunction "E_2") (pintype "passive"))
      (node (ref "Q208") (pin "3") (pinfunction "C_3") (pintype "passive"))
      (node (ref "Q210") (pin "3") (pinfunction "C_3") (pintype "passive"))
      (node (ref "Q411") (pin "3") (pinfunction "C_3") (pintype "passive"))
      (node (ref "Q414") (pin "3") (pinfunction "C_3") (pintype "passive"))
      (node (ref "R207") (pin "1") (pinfunction "1_1") (pintype "passive"))
      (node (ref "R208") (pin "1") (pinfunction "1_1") (pintype "passive"))
      (node (ref "R209") (pin "1") (pinfunction "1_1") (pintype "passive"))
      (node (ref "R210") (pin "1") (pinfunction "1_1") (pintype "passive"))
      (node (ref "R211") (pin "1") (pinfunction "1_1") (pintype "passive"))
      (node (ref "R212") (pin "1") (pinfunction "1_1") (pintype "passive"))
      (node (ref "R223") (pin "1") (pinfunction "1_1") (pintype "passive"))
      (node (ref "R224") (pin "1") (pinfunction "1_1") (pintype "passive"))
      (node (ref "R301") (pin "1") (pinfunction "1_1") (pintype "passive"))
      (node (ref "R308") (pin "1") (pinfunction "1_1") (pintype "passive"))
      (node (ref "R311") (pin "1") (pinfunction "1_1") (pintype "passive"))
      (node (ref "U201") (pin "11") (pinfunction "GND_11") (pintype "bidirectional"))
      (node (ref "U201") (pin "4") (pinfunction "RS2_4") (pintype "bidirectional"))
      (node (ref "U201") (pin "5") (pinfunction "RS1_5") (pintype "bidirectional"))
      (node (ref "U202") (pin "11") (pinfunction "GND_11") (pintype "bidirectional"))
      (node (ref "U202") (pin "4") (pinfunction "RS2_4") (pintype "bidirectional"))
      (node (ref "U202") (pin "5") (pinfunction "RS1_5") (pintype "bidirectional"))
      (node (ref "U203") (pin "3") (pinfunction "+IN_3") (pintype "input"))
      (node (ref "U204") (pin "3") (pinfunction "+IN_3") (pintype "input"))
      (node (ref "U205") (pin "5") (pinfunction "REF_5") (pintype "passive"))
      (node (ref "U206") (pin "5") (pinfunction "REF_5") (pintype "passive"))
      (node (ref "U207") (pin "5") (pinfunction "REF_5") (pintype "passive"))
      (node (ref "U208") (pin "5") (pinfunction "REF_5") (pintype "passive"))
      (node (ref "U209") (pin "4") (pinfunction "GND_4") (pintype "bidirectional"))
      (node (ref "U210") (pin "4") (pinfunction "GND_4") (pintype "bidirectional"))
      (node (ref "U301") (pin "11") (pinfunction "12/15_11") (pintype "input"))
      (node (ref "U301") (pin "14") (pinfunction "GND_14") (pintype "power_in"))
      (node (ref "U301") (pin "2") (pinfunction "AGND_2") (pintype "power_in"))
      (node (ref "U302") (pin "2") (pinfunction "GND_2") (pintype "power_in"))
      (node (ref "U303") (pin "3") (pinfunction "GND_3") (pintype "power_in"))
      (node (ref "U304") (pin "3") (pinfunction "GND_3") (pintype "power_in"))
      (node (ref "U305") (pin "5") (pinfunction "REF_5") (pintype "passive"))
      (node (ref "U306") (pin "4") (pinfunction "GND_4") (pintype "bidirectional"))
      (node (ref "U307") (pin "4") (pinfunction "GND_4") (pintype "bidirectional"))
      (node (ref "U401") (pin "5") (pinfunction "GND_5") (pintype "power_in"))
      (node (ref "U402") (pin "5") (pinfunction "GND_5") (pintype "power_in"))
      (node (ref "U403") (pin "5") (pinfunction "GND_5") (pintype "power_in"))
      (node (ref "U404") (pin "5") (pinfunction "GND_5") (pintype "power_in"))
      (node (ref "U405") (pin "5") (pinfunction "GND_5") (pintype "power_in"))
      (node (ref "U406") (pin "5") (pinfunction "GND_5") (pintype "power_in"))
      (node (ref "U407") (pin "2") (pinfunction "C1_2") (pintype "input"))
      (node (ref "U407") (pin "3") (pinfunction "C2_3") (pintype "input"))
    )
    (net (code "38") (name "GNDI") (class "Default")
      (node (ref "C419") (pin "2") (pinfunction "2_2") (pintype "passive"))
      (node (ref "C422") (pin "2") (pinfunction "2_2") (pintype "passive"))
      (node (ref "C425") (pin "2") (pinfunction "2_2") (pintype "passive"))
      (node (ref "C428") (pin "2") (pinfunction "2_2") (pintype "passive"))
      (node (ref "PS301") (pin "5") (pinfunction "-VO_5") (pintype "power_in"))
      (node (ref "Q401") (pin "3") (pinfunction "C_3") (pintype "passive"))
      (node (ref "Q402") (pin "3") (pinfunction "C_3") (pintype "passive"))
      (node (ref "Q403") (pin "3") (pinfunction "C_3") (pintype "passive"))
      (node (ref "Q404") (pin "3") (pinfunction "C_3") (pintype "passive"))
      (node (ref "Q405") (pin "3") (pinfunction "C_3") (pintype "passive"))
      (node (ref "Q406") (pin "3") (pinfunction "C_3") (pintype "passive"))
      (node (ref "Q407") (pin "3") (pinfunction "C_3") (pintype "passive"))
      (node (ref "Q408") (pin "3") (pinfunction "C_3") (pintype "passive"))
      (node (ref "Q409") (pin "3") (pinfunction "C_3") (pintype "passive"))
      (node (ref "Q410") (pin "3") (pinfunction "C_3") (pintype "passive"))
      (node (ref "Q412") (pin "3") (pinfunction "C_3") (pintype "passive"))
      (node (ref "Q413") (pin "3") (pinfunction "C_3") (pintype "passive"))
      (node (ref "U401") (pin "2") (pinfunction "C1_2") (pintype "input"))
      (node (ref "U401") (pin "3") (pinfunction "C2_3") (pintype "input"))
      (node (ref "U402") (pin "2") (pinfunction "C1_2") (pintype "input"))
      (node (ref "U402") (pin "3") (pinfunction "C2_3") (pintype "input"))
      (node (ref "U403") (pin "2") (pinfunction "C1_2") (pintype "input"))
      (node (ref "U403") (pin "3") (pinfunction "C2_3") (pintype "input"))
      (node (ref "U404") (pin "2") (pinfunction "C1_2") (pintype "input"))
      (node (ref "U404") (pin "3") (pinfunction "C2_3") (pintype "input"))
      (node (ref "U405") (pin "2") (pinfunction "C1_2") (pintype "input"))
      (node (ref "U405") (pin "3") (pinfunction "C2_3") (pintype "input"))
      (node (ref "U406") (pin "2") (pinfunction "C1_2") (pintype "input"))
      (node (ref "U406") (pin "3") (pinfunction "C2_3") (pintype "input"))
      (node (ref "U407") (pin "5") (pinfunction "GND_5") (pintype "power_in"))
    )
    (net (code "39") (name "LATCH_DAC") (class "Default")
      (node (ref "C413") (pin "1") (pinfunction "1_1") (pintype "passive"))
      (node (ref "R413") (pin "1") (pinfunction "1_1") (pintype "passive"))
      (node (ref "U201") (pin "7") (pinfunction "LATCH_7") (pintype "bidirectional"))
      (node (ref "U202") (pin "7") (pinfunction "LATCH_7") (pintype "bidirectional"))
      (node (ref "U401") (pin "6") (pinfunction "VO2_6") (pintype "output"))
    )
    (net (code "40") (name "LATCH_DAC_I") (class "Default")
      (node (ref "Q405") (pin "1") (pinfunction "B_1") (pintype "passive"))
    )
    (net (code "41") (name "LGATE_1") (class "Default")
      (node (ref "Q211") (pin "3") (pinfunction "G_3") (pintype "passive"))
      (node (ref "R229") (pin "2") (pinfunction "2_2") (pintype "passive"))
    )
    (net (code "42") (name "LGATE_2") (class "Default")
      (node (ref "Q212") (pin "3") (pinfunction "G_3") (pintype "passive"))
      (node (ref "R230") (pin "2") (pinfunction "2_2") (pintype "passive"))
    )
    (net (code "43") (name "MISO") (class "Default")
      (node (ref "Q411") (pin "1") (pinfunction "B_1") (pintype "passive"))
      (node (ref "U209") (pin "6") (pinfunction "SDO_6") (pintype "output"))
      (node (ref "U210") (pin "6") (pinfunction "SDO_6") (pintype "output"))
      (node (ref "U306") (pin "6") (pinfunction "SDO_6") (pintype "output"))
      (node (ref "U307") (pin "6") (pinfunction "SDO_6") (pintype "output"))
    )
    (net (code "44") (name "MISO_I") (class "Default")
      (node (ref "C425") (pin "1") (pinfunction "1_1") (pintype "passive"))
      (node (ref "R425") (pin "1") (pinfunction "1_1") (pintype "passive"))
      (node (ref "U407") (pin "7") (pinfunction "VO1_7") (pintype "output"))
    )
    (net (code "45") (name "MOSI") (class "Default")
      (node (ref "C416") (pin "1") (pinfunction "1_1") (pintype "passive"))
      (node (ref "R416") (pin "1") (pinfunction "1_1") (pintype "passive"))
      (node (ref "U201") (pin "9") (pinfunction "SDI_9") (pintype "bidirectional"))
      (node (ref "U209") (pin "5") (pinfunction "SDI_5") (pintype "input"))
      (node (ref "U210") (pin "5") (pinfunction "SDI_5") (pintype "input"))
      (node (ref "U306") (pin "5") (pinfunction "SDI_5") (pintype "input"))
      (node (ref "U307") (pin "5") (pinfunction "SDI_5") (pintype "input"))
      (node (ref "U404") (pin "6") (pinfunction "VO2_6") (pintype "output"))
    )
    (net (code "46") (name "MOSI_I") (class "Default")
      (node (ref "Q408") (pin "1") (pinfunction "B_1") (pintype "passive"))
    )
    (net (code "47") (name "Net-(C320-Pad1)") (class "Default")
      (node (ref "C320") (pin "1") (pinfunction "1_1") (pintype "passive"))
      (node (ref "R303") (pin "1") (pinfunction "1_1") (pintype "passive"))
    )
    (net (code "48") (name "Net-(D201-C1A2)") (class "Default")
      (node (ref "D201") (pin "3") (pinfunction "C1A2_3") (pintype "passive"))
      (node (ref "R255") (pin "1") (pinfunction "1_1") (pintype "passive"))
      (node (ref "U205") (pin "6") (pinfunction "OUT_6") (pintype "output"))
    )
    (net (code "49") (name "Net-(D202-C1A2)") (class "Default")
      (node (ref "D202") (pin "3") (pinfunction "C1A2_3") (pintype "passive"))
      (node (ref "R256") (pin "1") (pinfunction "1_1") (pintype "passive"))
      (node (ref "U206") (pin "6") (pinfunction "OUT_6") (pintype "output"))
    )
    (net (code "50") (name "Net-(D203-C1A2)") (class "Default")
      (node (ref "D203") (pin "3") (pinfunction "C1A2_3") (pintype "passive"))
      (node (ref "R257") (pin "1") (pinfunction "1_1") (pintype "passive"))
      (node (ref "U207") (pin "6") (pinfunction "OUT_6") (pintype "output"))
    )
    (net (code "51") (name "Net-(D204-C1A2)") (class "Default")
      (node (ref "D204") (pin "3") (pinfunction "C1A2_3") (pintype "passive"))
      (node (ref "R258") (pin "1") (pinfunction "1_1") (pintype "passive"))
      (node (ref "U208") (pin "6") (pinfunction "OUT_6") (pintype "output"))
    )
    (net (code "52") (name "Net-(D303-C1A2)") (class "Default")
      (node (ref "C324") (pin "1") (pinfunction "1_1") (pintype "passive"))
      (node (ref "D303") (pin "3") (pinfunction "C1A2_3") (pintype "passive"))
      (node (ref "R310") (pin "2") (pinfunction "2_2") (pintype "passive"))
      (node (ref "U307") (pin "2") (pinfunction "CH0_2") (pintype "input"))
    )
    (net (code "53") (name "Net-(MOV301-Pad2)") (class "Default")
      (node (ref "MOV301") (pin "2") (pinfunction "2_2") (pintype "passive"))
      (node (ref "MOV302") (pin "1") (pinfunction "1_1") (pintype "passive"))
    )
    (net (code "54") (name "Net-(MOV302-Pad2)") (class "Default")
      (node (ref "MOV302") (pin "2") (pinfunction "2_2") (pintype "passive"))
      (node (ref "MOV303") (pin "1") (pinfunction "1_1") (pintype "passive"))
    )
    (net (code "55") (name "Net-(MOV303-Pad2)") (class "Default")
      (node (ref "MOV303") (pin "2") (pinfunction "2_2") (pintype "passive"))
      (node (ref "MOV304") (pin "1") (pinfunction "1_1") (pintype "passive"))
    )
    (net (code "56") (name "Net-(Q201-G)") (class "Default")
      (node (ref "Q201") (pin "4") (pinfunction "G_4") (pintype "passive"))
      (node (ref "R232") (pin "2") (pinfunction "2_2") (pintype "passive"))
    )
    (net (code "57") (name "Net-(Q202-G)") (class "Default")
      (node (ref "Q202") (pin "4") (pinfunction "G_4") (pintype "passive"))
      (node (ref "R234") (pin "2") (pinfunction "2_2") (pintype "passive"))
    )
    (net (code "58") (name "Net-(Q203-B)") (class "Default")
      (node (ref "Q203") (pin "1") (pinfunction "B_1") (pintype "passive"))
      (node (ref "R231") (pin "2") (pinfunction "2_2") (pintype "passive"))
      (node (ref "R235") (pin "1") (pinfunction "1_1") (pintype "passive"))
    )
    (net (code "59") (name "Net-(Q203-C)") (class "Default")
      (node (ref "Q203") (pin "3") (pinfunction "C_3") (pintype "passive"))
      (node (ref "Q207") (pin "1") (pinfunction "B_1") (pintype "passive"))
      (node (ref "Q208") (pin "1") (pinfunction "B_1") (pintype "passive"))
      (node (ref "R237") (pin "1") (pinfunction "1_1") (pintype "passive"))
    )
    (net (code "60") (name "Net-(Q204-B)") (class "Default")
      (node (ref "Q204") (pin "1") (pinfunction "B_1") (pintype "passive"))
      (node (ref "R233") (pin "2") (pinfunction "2_2") (pintype "passive"))
      (node (ref "R236") (pin "1") (pinfunction "1_1") (pintype "passive"))
    )
    (net (code "61") (name "Net-(Q204-C)") (class "Default")
      (node (ref "Q204") (pin "3") (pinfunction "C_3") (pintype "passive"))
      (node (ref "Q209") (pin "1") (pinfunction "B_1") (pintype "passive"))
      (node (ref "Q210") (pin "1") (pinfunction "B_1") (pintype "passive"))
      (node (ref "R239") (pin "1") (pinfunction "1_1") (pintype "passive"))
    )
    (net (code "62") (name "Net-(Q205-G)") (class "Default")
      (node (ref "Q205") (pin "4") (pinfunction "G_4") (pintype "passive"))
      (node (ref "R238") (pin "2") (pinfunction "2_2") (pintype "passive"))
    )
    (net (code "63") (name "Net-(Q206-G)") (class "Default")
      (node (ref "Q206") (pin "4") (pinfunction "G_4") (pintype "passive"))
      (node (ref "R240") (pin "2") (pinfunction "2_2") (pintype "passive"))
    )
    (net (code "64") (name "Net-(Q401-E)") (class "Default")
      (node (ref "Q401") (pin "2") (pinfunction "E_2") (pintype "passive"))
      (node (ref "R401") (pin "1") (pinfunction "1_1") (pintype "passive"))
      (node (ref "U401") (pin "1") (pinfunction "A1_1") (pintype "input"))
    )
    (net (code "65") (name "Net-(Q402-E)") (class "Default")
      (node (ref "Q402") (pin "2") (pinfunction "E_2") (pintype "passive"))
      (node (ref "R402") (pin "1") (pinfunction "1_1") (pintype "passive"))
      (node (ref "U402") (pin "1") (pinfunction "A1_1") (pintype "input"))
    )
    (net (code "66") (name "Net-(Q403-E)") (class "Default")
      (node (ref "Q403") (pin "2") (pinfunction "E_2") (pintype "passive"))
      (node (ref "R403") (pin "1") (pinfunction "1_1") (pintype "passive"))
      (node (ref "U403") (pin "1") (pinfunction "A1_1") (pintype "input"))
    )
    (net (code "67") (name "Net-(Q404-E)") (class "Default")
      (node (ref "Q404") (pin "2") (pinfunction "E_2") (pintype "passive"))
      (node (ref "R404") (pin "1") (pinfunction "1_1") (pintype "passive"))
      (node (ref "U404") (pin "1") (pinfunction "A1_1") (pintype "input"))
    )
    (net (code "68") (name "Net-(Q405-E)") (class "Default")
      (node (ref "Q405") (pin "2") (pinfunction "E_2") (pintype "passive"))
      (node (ref "R405") (pin "1") (pinfunction "1_1") (pintype "passive"))
      (node (ref "U401") (pin "4") (pinfunction "A2_4") (pintype "input"))
    )
    (net (code "69") (name "Net-(Q406-E)") (class "Default")
      (node (ref "Q406") (pin "2") (pinfunction "E_2") (pintype "passive"))
      (node (ref "R406") (pin "1") (pinfunction "1_1") (pintype "passive"))
      (node (ref "U402") (pin "4") (pinfunction "A2_4") (pintype "input"))
    )
    (net (code "70") (name "Net-(Q407-E)") (class "Default")
      (node (ref "Q407") (pin "2") (pinfunction "E_2") (pintype "passive"))
      (node (ref "R407") (pin "1") (pinfunction "1_1") (pintype "passive"))
      (node (ref "U403") (pin "4") (pinfunction "A2_4") (pintype "input"))
    )
    (net (code "71") (name "Net-(Q408-E)") (class "Default")
      (node (ref "Q408") (pin "2") (pinfunction "E_2") (pintype "passive"))
      (node (ref "R408") (pin "1") (pinfunction "1_1") (pintype "passive"))
      (node (ref "U404") (pin "4") (pinfunction "A2_4") (pintype "input"))
    )
    (net (code "72") (name "Net-(Q409-E)") (class "Default")
      (node (ref "Q409") (pin "2") (pinfunction "E_2") (pintype "passive"))
      (node (ref "R417") (pin "1") (pinfunction "1_1") (pintype "passive"))
      (node (ref "U405") (pin "1") (pinfunction "A1_1") (pintype "input"))
    )
    (net (code "73") (name "Net-(Q410-E)") (class "Default")
      (node (ref "Q410") (pin "2") (pinfunction "E_2") (pintype "passive"))
      (node (ref "R418") (pin "1") (pinfunction "1_1") (pintype "passive"))
      (node (ref "U406") (pin "1") (pinfunction "A1_1") (pintype "input"))
    )
    (net (code "74") (name "Net-(Q411-E)") (class "Default")
      (node (ref "Q411") (pin "2") (pinfunction "E_2") (pintype "passive"))
      (node (ref "R419") (pin "1") (pinfunction "1_1") (pintype "passive"))
      (node (ref "U407") (pin "1") (pinfunction "A1_1") (pintype "input"))
    )
    (net (code "75") (name "Net-(Q412-E)") (class "Default")
      (node (ref "Q412") (pin "2") (pinfunction "E_2") (pintype "passive"))
      (node (ref "R420") (pin "1") (pinfunction "1_1") (pintype "passive"))
      (node (ref "U405") (pin "4") (pinfunction "A2_4") (pintype "input"))
    )
    (net (code "76") (name "Net-(Q413-E)") (class "Default")
      (node (ref "Q413") (pin "2") (pinfunction "E_2") (pintype "passive"))
      (node (ref "R421") (pin "1") (pinfunction "1_1") (pintype "passive"))
      (node (ref "U406") (pin "4") (pinfunction "A2_4") (pintype "input"))
    )
    (net (code "77") (name "Net-(Q414-E)") (class "Default")
      (node (ref "Q414") (pin "2") (pinfunction "E_2") (pintype "passive"))
      (node (ref "R422") (pin "1") (pinfunction "1_1") (pintype "passive"))
      (node (ref "U407") (pin "4") (pinfunction "A2_4") (pintype "input"))
    )
    (net (code "78") (name "Net-(R251-Pad1)") (class "Default")
      (node (ref "R251") (pin "1") (pinfunction "1_1") (pintype "passive"))
      (node (ref "U205") (pin "8") (pinfunction "RG_8") (pintype "passive"))
    )
    (net (code "79") (name "Net-(R251-Pad2)") (class "Default")
      (node (ref "R251") (pin "2") (pinfunction "2_2") (pintype "passive"))
      (node (ref "U205") (pin "1") (pinfunction "RG_1") (pintype "passive"))
    )
    (net (code "80") (name "Net-(R252-Pad1)") (class "Default")
      (node (ref "R252") (pin "1") (pinfunction "1_1") (pintype "passive"))
      (node (ref "U206") (pin "8") (pinfunction "RG_8") (pintype "passive"))
    )
    (net (code "81") (name "Net-(R252-Pad2)") (class "Default")
      (node (ref "R252") (pin "2") (pinfunction "2_2") (pintype "passive"))
      (node (ref "U206") (pin "1") (pinfunction "RG_1") (pintype "passive"))
    )
    (net (code "82") (name "Net-(R253-Pad1)") (class "Default")
      (node (ref "R253") (pin "1") (pinfunction "1_1") (pintype "passive"))
      (node (ref "U207") (pin "8") (pinfunction "RG_8") (pintype "passive"))
    )
    (net (code "83") (name "Net-(R253-Pad2)") (class "Default")
      (node (ref "R253") (pin "2") (pinfunction "2_2") (pintype "passive"))
      (node (ref "U207") (pin "1") (pinfunction "RG_1") (pintype "passive"))
    )
    (net (code "84") (name "Net-(R254-Pad1)") (class "Default")
      (node (ref "R254") (pin "1") (pinfunction "1_1") (pintype "passive"))
      (node (ref "U208") (pin "8") (pinfunction "RG_8") (pintype "passive"))
    )
    (net (code "85") (name "Net-(R254-Pad2)") (class "Default")
      (node (ref "R254") (pin "2") (pinfunction "2_2") (pintype "passive"))
      (node (ref "U208") (pin "1") (pinfunction "RG_1") (pintype "passive"))
    )
    (net (code "86") (name "Net-(R302-Pad2)") (class "Default")
      (node (ref "R302") (pin "2") (pinfunction "2_2") (pintype "passive"))
      (node (ref "R305") (pin "1") (pinfunction "1_1") (pintype "passive"))
    )
    (net (code "87") (name "Net-(R304-Pad1)") (class "Default")
      (node (ref "R304") (pin "1") (pinfunction "1_1") (pintype "passive"))
      (node (ref "R305") (pin "2") (pinfunction "2_2") (pintype "passive"))
    )
    (net (code "88") (name "Net-(R304-Pad2)") (class "Default")
      (node (ref "R304") (pin "2") (pinfunction "2_2") (pintype "passive"))
      (node (ref "R306") (pin "2") (pinfunction "2_2") (pintype "passive"))
    )
    (net (code "89") (name "Net-(R306-Pad1)") (class "Default")
      (node (ref "R306") (pin "1") (pinfunction "1_1") (pintype "passive"))
      (node (ref "R307") (pin "2") (pinfunction "2_2") (pintype "passive"))
    )
    (net (code "90") (name "Net-(R309-Pad1)") (class "Default")
      (node (ref "R309") (pin "1") (pinfunction "1_1") (pintype "passive"))
      (node (ref "U305") (pin "8") (pinfunction "RG_8") (pintype "passive"))
    )
    (net (code "91") (name "Net-(R309-Pad2)") (class "Default")
      (node (ref "R309") (pin "2") (pinfunction "2_2") (pintype "passive"))
      (node (ref "U305") (pin "1") (pinfunction "RG_1") (pintype "passive"))
    )
    (net (code "92") (name "Net-(U201-C1)") (class "Default")
      (node (ref "C207") (pin "2") (pinfunction "2_2") (pintype "passive"))
      (node (ref "U201") (pin "20") (pinfunction "C1_20") (pintype "bidirectional"))
    )
    (net (code "93") (name "Net-(U201-C2)") (class "Default")
      (node (ref "C205") (pin "2") (pinfunction "2_2") (pintype "passive"))
      (node (ref "U201") (pin "21") (pinfunction "C2_21") (pintype "bidirectional"))
    )
    (net (code "94") (name "Net-(U201-VOUT)") (class "Default")
      (node (ref "U201") (pin "17") (pinfunction "VOUT_17") (pintype "bidirectional"))
      (node (ref "U203") (pin "5") (pinfunction "+IN_5") (pintype "input"))
    )
    (net (code "95") (name "Net-(U202-C1)") (class "Default")
      (node (ref "C208") (pin "2") (pinfunction "2_2") (pintype "passive"))
      (node (ref "U202") (pin "20") (pinfunction "C1_20") (pintype "bidirectional"))
    )
    (net (code "96") (name "Net-(U202-C2)") (class "Default")
      (node (ref "C206") (pin "2") (pinfunction "2_2") (pintype "passive"))
      (node (ref "U202") (pin "21") (pinfunction "C2_21") (pintype "bidirectional"))
    )
    (net (code "97") (name "Net-(U202-VOUT)") (class "Default")
      (node (ref "U202") (pin "17") (pinfunction "VOUT_17") (pintype "bidirectional"))
      (node (ref "U204") (pin "5") (pinfunction "+IN_5") (pintype "input"))
    )
    (net (code "98") (name "Net-(U203A--IN)") (class "Default")
      (node (ref "U203") (pin "1") (pinfunction "OUT_1") (pintype "output"))
      (node (ref "U203") (pin "2") (pinfunction "-IN_2") (pintype "input"))
    )
    (net (code "99") (name "Net-(U203B--IN)") (class "Default")
      (node (ref "R205") (pin "2") (pinfunction "2_2") (pintype "passive"))
      (node (ref "R207") (pin "2") (pinfunction "2_2") (pintype "passive"))
      (node (ref "R211") (pin "2") (pinfunction "2_2") (pintype "passive"))
      (node (ref "R213") (pin "1") (pinfunction "1_1") (pintype "passive"))
      (node (ref "R214") (pin "1") (pinfunction "1_1") (pintype "passive"))
      (node (ref "U203") (pin "6") (pinfunction "-IN_6") (pintype "input"))
    )
    (net (code "100") (name "Net-(U203B-OUT)") (class "Default")
      (node (ref "R213") (pin "2") (pinfunction "2_2") (pintype "passive"))
      (node (ref "R214") (pin "2") (pinfunction "2_2") (pintype "passive"))
      (node (ref "R219") (pin "1") (pinfunction "1_1") (pintype "passive"))
      (node (ref "U203") (pin "7") (pinfunction "OUT_7") (pintype "output"))
    )
    (net (code "101") (name "Net-(U203C-+IN)") (class "Default")
      (node (ref "R203") (pin "2") (pinfunction "2_2") (pintype "passive"))
      (node (ref "R209") (pin "2") (pinfunction "2_2") (pintype "passive"))
      (node (ref "U203") (pin "12") (pinfunction "+IN_12") (pintype "input"))
    )
    (net (code "102") (name "Net-(U203C--IN)") (class "Default")
      (node (ref "R201") (pin "2") (pinfunction "2_2") (pintype "passive"))
      (node (ref "R215") (pin "1") (pinfunction "1_1") (pintype "passive"))
      (node (ref "U203") (pin "11") (pinfunction "-IN_11") (pintype "input"))
    )
    (net (code "103") (name "Net-(U203C-OUT)") (class "Default")
      (node (ref "R215") (pin "2") (pinfunction "2_2") (pintype "passive"))
      (node (ref "R221") (pin "1") (pinfunction "1_1") (pintype "passive"))
      (node (ref "U203") (pin "10") (pinfunction "OUT_10") (pintype "output"))
    )
    (net (code "104") (name "Net-(U203D-+IN)") (class "Default")
      (node (ref "R219") (pin "2") (pinfunction "2_2") (pintype "passive"))
      (node (ref "R223") (pin "2") (pinfunction "2_2") (pintype "passive"))
      (node (ref "U203") (pin "14") (pinfunction "+IN_14") (pintype "input"))
    )
    (net (code "105") (name "Net-(U203D--IN)") (class "Default")
      (node (ref "R221") (pin "2") (pinfunction "2_2") (pintype "passive"))
      (node (ref "R225") (pin "1") (pinfunction "1_1") (pintype "passive"))
      (node (ref "U203") (pin "15") (pinfunction "-IN_15") (pintype "input"))
    )
    (net (code "106") (name "Net-(U203D-OUT)") (class "Default")
      (node (ref "R225") (pin "2") (pinfunction "2_2") (pintype "passive"))
      (node (ref "R227") (pin "2") (pinfunction "2_2") (pintype "passive"))
      (node (ref "R229") (pin "1") (pinfunction "1_1") (pintype "passive"))
      (node (ref "U203") (pin "16") (pinfunction "OUT_16") (pintype "output"))
    )
    (net (code "107") (name "Net-(U204A--IN)") (class "Default")
      (node (ref "U204") (pin "1") (pinfunction "OUT_1") (pintype "output"))
      (node (ref "U204") (pin "2") (pinfunction "-IN_2") (pintype "input"))
    )
    (net (code "108") (name "Net-(U204B--IN)") (class "Default")
      (node (ref "R206") (pin "2") (pinfunction "2_2") (pintype "passive"))
      (node (ref "R208") (pin "2") (pinfunction "2_2") (pintype "passive"))
      (node (ref "R212") (pin "2") (pinfunction "2_2") (pintype "passive"))
      (node (ref "R216") (pin "1") (pinfunction "1_1") (pintype "passive"))
      (node (ref "R217") (pin "1") (pinfunction "1_1") (pintype "passive"))
      (node (ref "U204") (pin "6") (pinfunction "-IN_6") (pintype "input"))
    )
    (net (code "109") (name "Net-(U204B-OUT)") (class "Default")
      (node (ref "R216") (pin "2") (pinfunction "2_2") (pintype "passive"))
      (node (ref "R217") (pin "2") (pinfunction "2_2") (pintype "passive"))
      (node (ref "R220") (pin "1") (pinfunction "1_1") (pintype "passive"))
      (node (ref "U204") (pin "7") (pinfunction "OUT_7") (pintype "output"))
    )
    (net (code "110") (name "Net-(U204C-+IN)") (class "Default")
      (node (ref "R204") (pin "2") (pinfunction "2_2") (pintype "passive"))
      (node (ref "R210") (pin "2") (pinfunction "2_2") (pintype "passive"))
      (node (ref "U204") (pin "12") (pinfunction "+IN_12") (pintype "input"))
    )
    (net (code "111") (name "Net-(U204C--IN)") (class "Default")
      (node (ref "R202") (pin "2") (pinfunction "2_2") (pintype "passive"))
      (node (ref "R218") (pin "1") (pinfunction "1_1") (pintype "passive"))
      (node (ref "U204") (pin "11") (pinfunction "-IN_11") (pintype "input"))
    )
    (net (code "112") (name "Net-(U204C-OUT)") (class "Default")
      (node (ref "R218") (pin "2") (pinfunction "2_2") (pintype "passive"))
      (node (ref "R222") (pin "1") (pinfunction "1_1") (pintype "passive"))
      (node (ref "U204") (pin "10") (pinfunction "OUT_10") (pintype "output"))
    )
    (net (code "113") (name "Net-(U204D-+IN)") (class "Default")
      (node (ref "R220") (pin "2") (pinfunction "2_2") (pintype "passive"))
      (node (ref "R224") (pin "2") (pinfunction "2_2") (pintype "passive"))
      (node (ref "U204") (pin "14") (pinfunction "+IN_14") (pintype "input"))
    )
    (net (code "114") (name "Net-(U204D--IN)") (class "Default")
      (node (ref "R222") (pin "2") (pinfunction "2_2") (pintype "passive"))
      (node (ref "R226") (pin "1") (pinfunction "1_1") (pintype "passive"))
      (node (ref "U204") (pin "15") (pinfunction "-IN_15") (pintype "input"))
    )
    (net (code "115") (name "Net-(U204D-OUT)") (class "Default")
      (node (ref "R226") (pin "2") (pinfunction "2_2") (pintype "passive"))
      (node (ref "R228") (pin "2") (pinfunction "2_2") (pintype "passive"))
      (node (ref "R230") (pin "1") (pinfunction "1_1") (pintype "passive"))
      (node (ref "U204") (pin "16") (pinfunction "OUT_16") (pintype "output"))
    )
    (net (code "116") (name "Net-(U209-CH0)") (class "Default")
      (node (ref "C225") (pin "1") (pinfunction "1_1") (pintype "passive"))
      (node (ref "R255") (pin "2") (pinfunction "2_2") (pintype "passive"))
      (node (ref "U209") (pin "2") (pinfunction "CH0_2") (pintype "input"))
    )
    (net (code "117") (name "Net-(U209-CH1)") (class "Default")
      (node (ref "C226") (pin "1") (pinfunction "1_1") (pintype "passive"))
      (node (ref "R256") (pin "2") (pinfunction "2_2") (pintype "passive"))
      (node (ref "U209") (pin "3") (pinfunction "CH1_3") (pintype "input"))
    )
    (net (code "118") (name "Net-(U210-CH0)") (class "Default")
      (node (ref "C227") (pin "1") (pinfunction "1_1") (pintype "passive"))
      (node (ref "R257") (pin "2") (pinfunction "2_2") (pintype "passive"))
      (node (ref "U210") (pin "2") (pinfunction "CH0_2") (pintype "input"))
    )
    (net (code "119") (name "Net-(U210-CH1)") (class "Default")
      (node (ref "C228") (pin "1") (pinfunction "1_1") (pintype "passive"))
      (node (ref "R258") (pin "2") (pinfunction "2_2") (pintype "passive"))
      (node (ref "U210") (pin "3") (pinfunction "CH1_3") (pintype "input"))
    )
    (net (code "120") (name "Net-(U301-CC+)") (class "Default")
      (node (ref "C305") (pin "2") (pinfunction "2_2") (pintype "passive"))
      (node (ref "U301") (pin "1") (pinfunction "CC+_1") (pintype "passive"))
    )
    (net (code "121") (name "Net-(U301-CC-)") (class "Default")
      (node (ref "C307") (pin "1") (pinfunction "1_1") (pintype "passive"))
      (node (ref "U301") (pin "8") (pinfunction "CC-_8") (pintype "passive"))
    )
    (net (code "122") (name "Net-(U301-LX+)") (class "Default")
      (node (ref "D301") (pin "A") (pinfunction "A_A") (pintype "passive"))
      (node (ref "L302") (pin "2") (pinfunction "2_2") (pintype "passive"))
      (node (ref "U301") (pin "15") (pinfunction "LX+_15") (pintype "passive"))
    )
    (net (code "123") (name "Net-(U301-LX-)") (class "Default")
      (node (ref "D302") (pin "C") (pinfunction "C_C") (pintype "passive"))
      (node (ref "L301") (pin "1") (pinfunction "1_1") (pintype "passive"))
      (node (ref "U301") (pin "10") (pinfunction "LX-_10") (pintype "passive"))
    )
    (net (code "124") (name "Net-(U301-SS)") (class "Default")
      (node (ref "C304") (pin "+") (pinfunction "+_+") (pintype "passive"))
      (node (ref "U301") (pin "7") (pinfunction "SS_7") (pintype "passive"))
    )
    (net (code "125") (name "Net-(U301-VREF)") (class "Default")
      (node (ref "C306") (pin "+") (pinfunction "+_+") (pintype "passive"))
      (node (ref "U301") (pin "6") (pinfunction "VREF_6") (pintype "power_in"))
    )
    (net (code "126") (name "Net-(U302-BYP)") (class "Default")
      (node (ref "C314") (pin "1") (pinfunction "1_1") (pintype "passive"))
      (node (ref "U302") (pin "4") (pinfunction "BYP_4") (pintype "power_in"))
    )
    (net (code "127") (name "Net-(U303-VO)") (class "Default")
      (node (ref "C318") (pin "+") (pinfunction "+_+") (pintype "passive"))
      (node (ref "U303") (pin "2") (pinfunction "VO_2") (pintype "output"))
      (node (ref "U306") (pin "2") (pinfunction "CH0_2") (pintype "input"))
    )
    (net (code "128") (name "Net-(U304-VO)") (class "Default")
      (node (ref "C319") (pin "+") (pinfunction "+_+") (pintype "passive"))
      (node (ref "U304") (pin "2") (pinfunction "VO_2") (pintype "output"))
      (node (ref "U306") (pin "3") (pinfunction "CH1_3") (pintype "input"))
    )
    (net (code "129") (name "Net-(U305-+)") (class "Default")
      (node (ref "R307") (pin "1") (pinfunction "1_1") (pintype "passive"))
      (node (ref "R308") (pin "2") (pinfunction "2_2") (pintype "passive"))
      (node (ref "U305") (pin "3") (pinfunction "+_3") (pintype "input"))
    )
    (net (code "130") (name "Net-(U305-OUT)") (class "Default")
      (node (ref "R310") (pin "1") (pinfunction "1_1") (pintype "passive"))
      (node (ref "U305") (pin "6") (pinfunction "OUT_6") (pintype "output"))
    )
    (net (code "131") (name "Net-(U307-CH1)") (class "Default")
      (node (ref "R311") (pin "2") (pinfunction "2_2") (pintype "passive"))
      (node (ref "U307") (pin "3") (pinfunction "CH1_3") (pintype "input"))
    )
    (net (code "132") (name "SCK") (class "Default")
      (node (ref "C412") (pin "1") (pinfunction "1_1") (pintype "passive"))
      (node (ref "R412") (pin "1") (pinfunction "1_1") (pintype "passive"))
      (node (ref "U201") (pin "8") (pinfunction "SCK_8") (pintype "bidirectional"))
      (node (ref "U202") (pin "8") (pinfunction "SCK_8") (pintype "bidirectional"))
      (node (ref "U209") (pin "7") (pinfunction "SCK_7") (pintype "input"))
      (node (ref "U210") (pin "7") (pinfunction "SCK_7") (pintype "input"))
      (node (ref "U306") (pin "7") (pinfunction "SCK_7") (pintype "input"))
      (node (ref "U307") (pin "7") (pinfunction "SCK_7") (pintype "input"))
      (node (ref "U404") (pin "7") (pinfunction "VO1_7") (pintype "output"))
    )
    (net (code "133") (name "SCK_I") (class "Default")
      (node (ref "Q404") (pin "1") (pinfunction "B_1") (pintype "passive"))
    )
    (net (code "134") (name "SDO_DAC1") (class "Default")
      (node (ref "U201") (pin "10") (pinfunction "SDO_10") (pintype "bidirectional"))
      (node (ref "U202") (pin "9") (pinfunction "SDI_9") (pintype "bidirectional"))
    )
    (net (code "135") (name "SDO_DAC2") (class "Default")
      (node (ref "U202") (pin "10") (pinfunction "SDO_10") (pintype "bidirectional"))
    )
    (net (code "136") (name "VREF1") (class "Default")
      (node (ref "C313") (pin "1") (pinfunction "1_1") (pintype "passive"))
      (node (ref "R205") (pin "1") (pinfunction "1_1") (pintype "passive"))
      (node (ref "U201") (pin "14") (pinfunction "REF_OUT_14") (pintype "bidirectional"))
      (node (ref "U201") (pin "15") (pinfunction "REF_IN_15") (pintype "bidirectional"))
      (node (ref "U302") (pin "1") (pinfunction "VIN_1") (pintype "power_in"))
      (node (ref "U302") (pin "3") (pinfunction "ON/OFF_3") (pintype "input"))
    )
    (net (code "137") (name "VREF2") (class "Default")
      (node (ref "R206") (pin "1") (pinfunction "1_1") (pintype "passive"))
      (node (ref "U202") (pin "14") (pinfunction "REF_OUT_14") (pintype "bidirectional"))
      (node (ref "U202") (pin "15") (pinfunction "REF_IN_15") (pintype "bidirectional"))
    )
    (net (code "138") (name "VSENSE+") (class "Default")
      (node (ref "MOV301") (pin "1") (pinfunction "1_1") (pintype "passive"))
      (node (ref "R302") (pin "1") (pinfunction "1_1") (pintype "passive"))
      (node (ref "X301") (pin "1") (pinfunction "1_1") (pintype "passive"))
    )
    (net (code "139") (name "VSENSE-") (class "Default")
      (node (ref "MOV304") (pin "2") (pinfunction "2_2") (pintype "passive"))
      (node (ref "U305") (pin "2") (pinfunction "-_2") (pintype "input"))
      (node (ref "X301") (pin "4") (pinfunction "1_4") (pintype "passive"))
    )
    (net (code "140") (name "unconnected-(J301-Pad2)") (class "Default")
      (node (ref "J301") (pin "2") (pinfunction "2_2") (pintype "passive"))
    )
    (net (code "141") (name "unconnected-(JP301-Pad1)") (class "Default")
      (node (ref "JP301") (pin "1") (pinfunction "1_1") (pintype "passive"))
    )
    (net (code "142") (name "unconnected-(JP301-Pad2)") (class "Default")
      (node (ref "JP301") (pin "2") (pinfunction "2_2") (pintype "passive"))
    )
    (net (code "143") (name "unconnected-(JP301-Pad3)") (class "Default")
      (node (ref "JP301") (pin "3") (pinfunction "3_3") (pintype "passive"))
    )
    (net (code "144") (name "unconnected-(JP301-Pad4)") (class "Default")
      (node (ref "JP301") (pin "4") (pinfunction "4_4") (pintype "passive"))
    )
    (net (code "145") (name "unconnected-(JP301-Pad5)") (class "Default")
      (node (ref "JP301") (pin "5") (pinfunction "5_5") (pintype "passive"))
    )
    (net (code "146") (name "unconnected-(JP301-Pad6)") (class "Default")
      (node (ref "JP301") (pin "6") (pinfunction "6_6") (pintype "passive"))
    )
    (net (code "147") (name "unconnected-(JP301-Pad7)") (class "Default")
      (node (ref "JP301") (pin "7") (pinfunction "7_7") (pintype "passive"))
    )
    (net (code "148") (name "unconnected-(JP301-Pad8)") (class "Default")
      (node (ref "JP301") (pin "8") (pinfunction "8_8") (pintype "passive"))
    )
    (net (code "149") (name "unconnected-(JP301-Pad9)") (class "Default")
      (node (ref "JP301") (pin "9") (pinfunction "9_9") (pintype "passive"))
    )
    (net (code "150") (name "unconnected-(JP301-Pad10)") (class "Default")
      (node (ref "JP301") (pin "10") (pinfunction "10_10") (pintype "passive"))
    )
    (net (code "151") (name "unconnected-(JP301-Pad11)") (class "Default")
      (node (ref "JP301") (pin "11") (pinfunction "11_11") (pintype "passive"))
    )
    (net (code "152") (name "unconnected-(JP301-Pad12)") (class "Default")
      (node (ref "JP301") (pin "12") (pinfunction "12_12") (pintype "passive"))
    )
    (net (code "153") (name "unconnected-(JP301-Pad13)") (class "Default")
      (node (ref "JP301") (pin "13") (pinfunction "13_13") (pintype "passive"))
    )
    (net (code "154") (name "unconnected-(JP301-Pad14)") (class "Default")
      (node (ref "JP301") (pin "14") (pinfunction "14_14") (pintype "passive"))
    )
    (net (code "155") (name "unconnected-(JP301-Pad15)") (class "Default")
      (node (ref "JP301") (pin "15") (pinfunction "15_15") (pintype "passive"))
    )
    (net (code "156") (name "unconnected-(JP301-Pad16)") (class "Default")
      (node (ref "JP301") (pin "16") (pinfunction "16_16") (pintype "passive"))
    )
    (net (code "157") (name "unconnected-(U201-BST-Pad19)") (class "Default")
      (node (ref "U201") (pin "19") (pinfunction "BST_19") (pintype "bidirectional"))
    )
    (net (code "158") (name "unconnected-(U201-IOUT-Pad18)") (class "Default")
      (node (ref "U201") (pin "18") (pinfunction "IOUT_18") (pintype "bidirectional"))
    )
    (net (code "159") (name "unconnected-(U201-O_TRIM-Pad16)") (class "Default")
      (node (ref "U201") (pin "16") (pinfunction "O_TRIM_16") (pintype "bidirectional"))
    )
    (net (code "160") (name "unconnected-(U202-BST-Pad19)") (class "Default")
      (node (ref "U202") (pin "19") (pinfunction "BST_19") (pintype "bidirectional"))
    )
    (net (code "161") (name "unconnected-(U202-IOUT-Pad18)") (class "Default")
      (node (ref "U202") (pin "18") (pinfunction "IOUT_18") (pintype "bidirectional"))
    )
    (net (code "162") (name "unconnected-(U202-O_TRIM-Pad16)") (class "Default")
      (node (ref "U202") (pin "16") (pinfunction "O_TRIM_16") (pintype "bidirectional"))
    )
  )
)
